# design.net
KiCad netlist of a schematic drawn in EasyEDA Pro
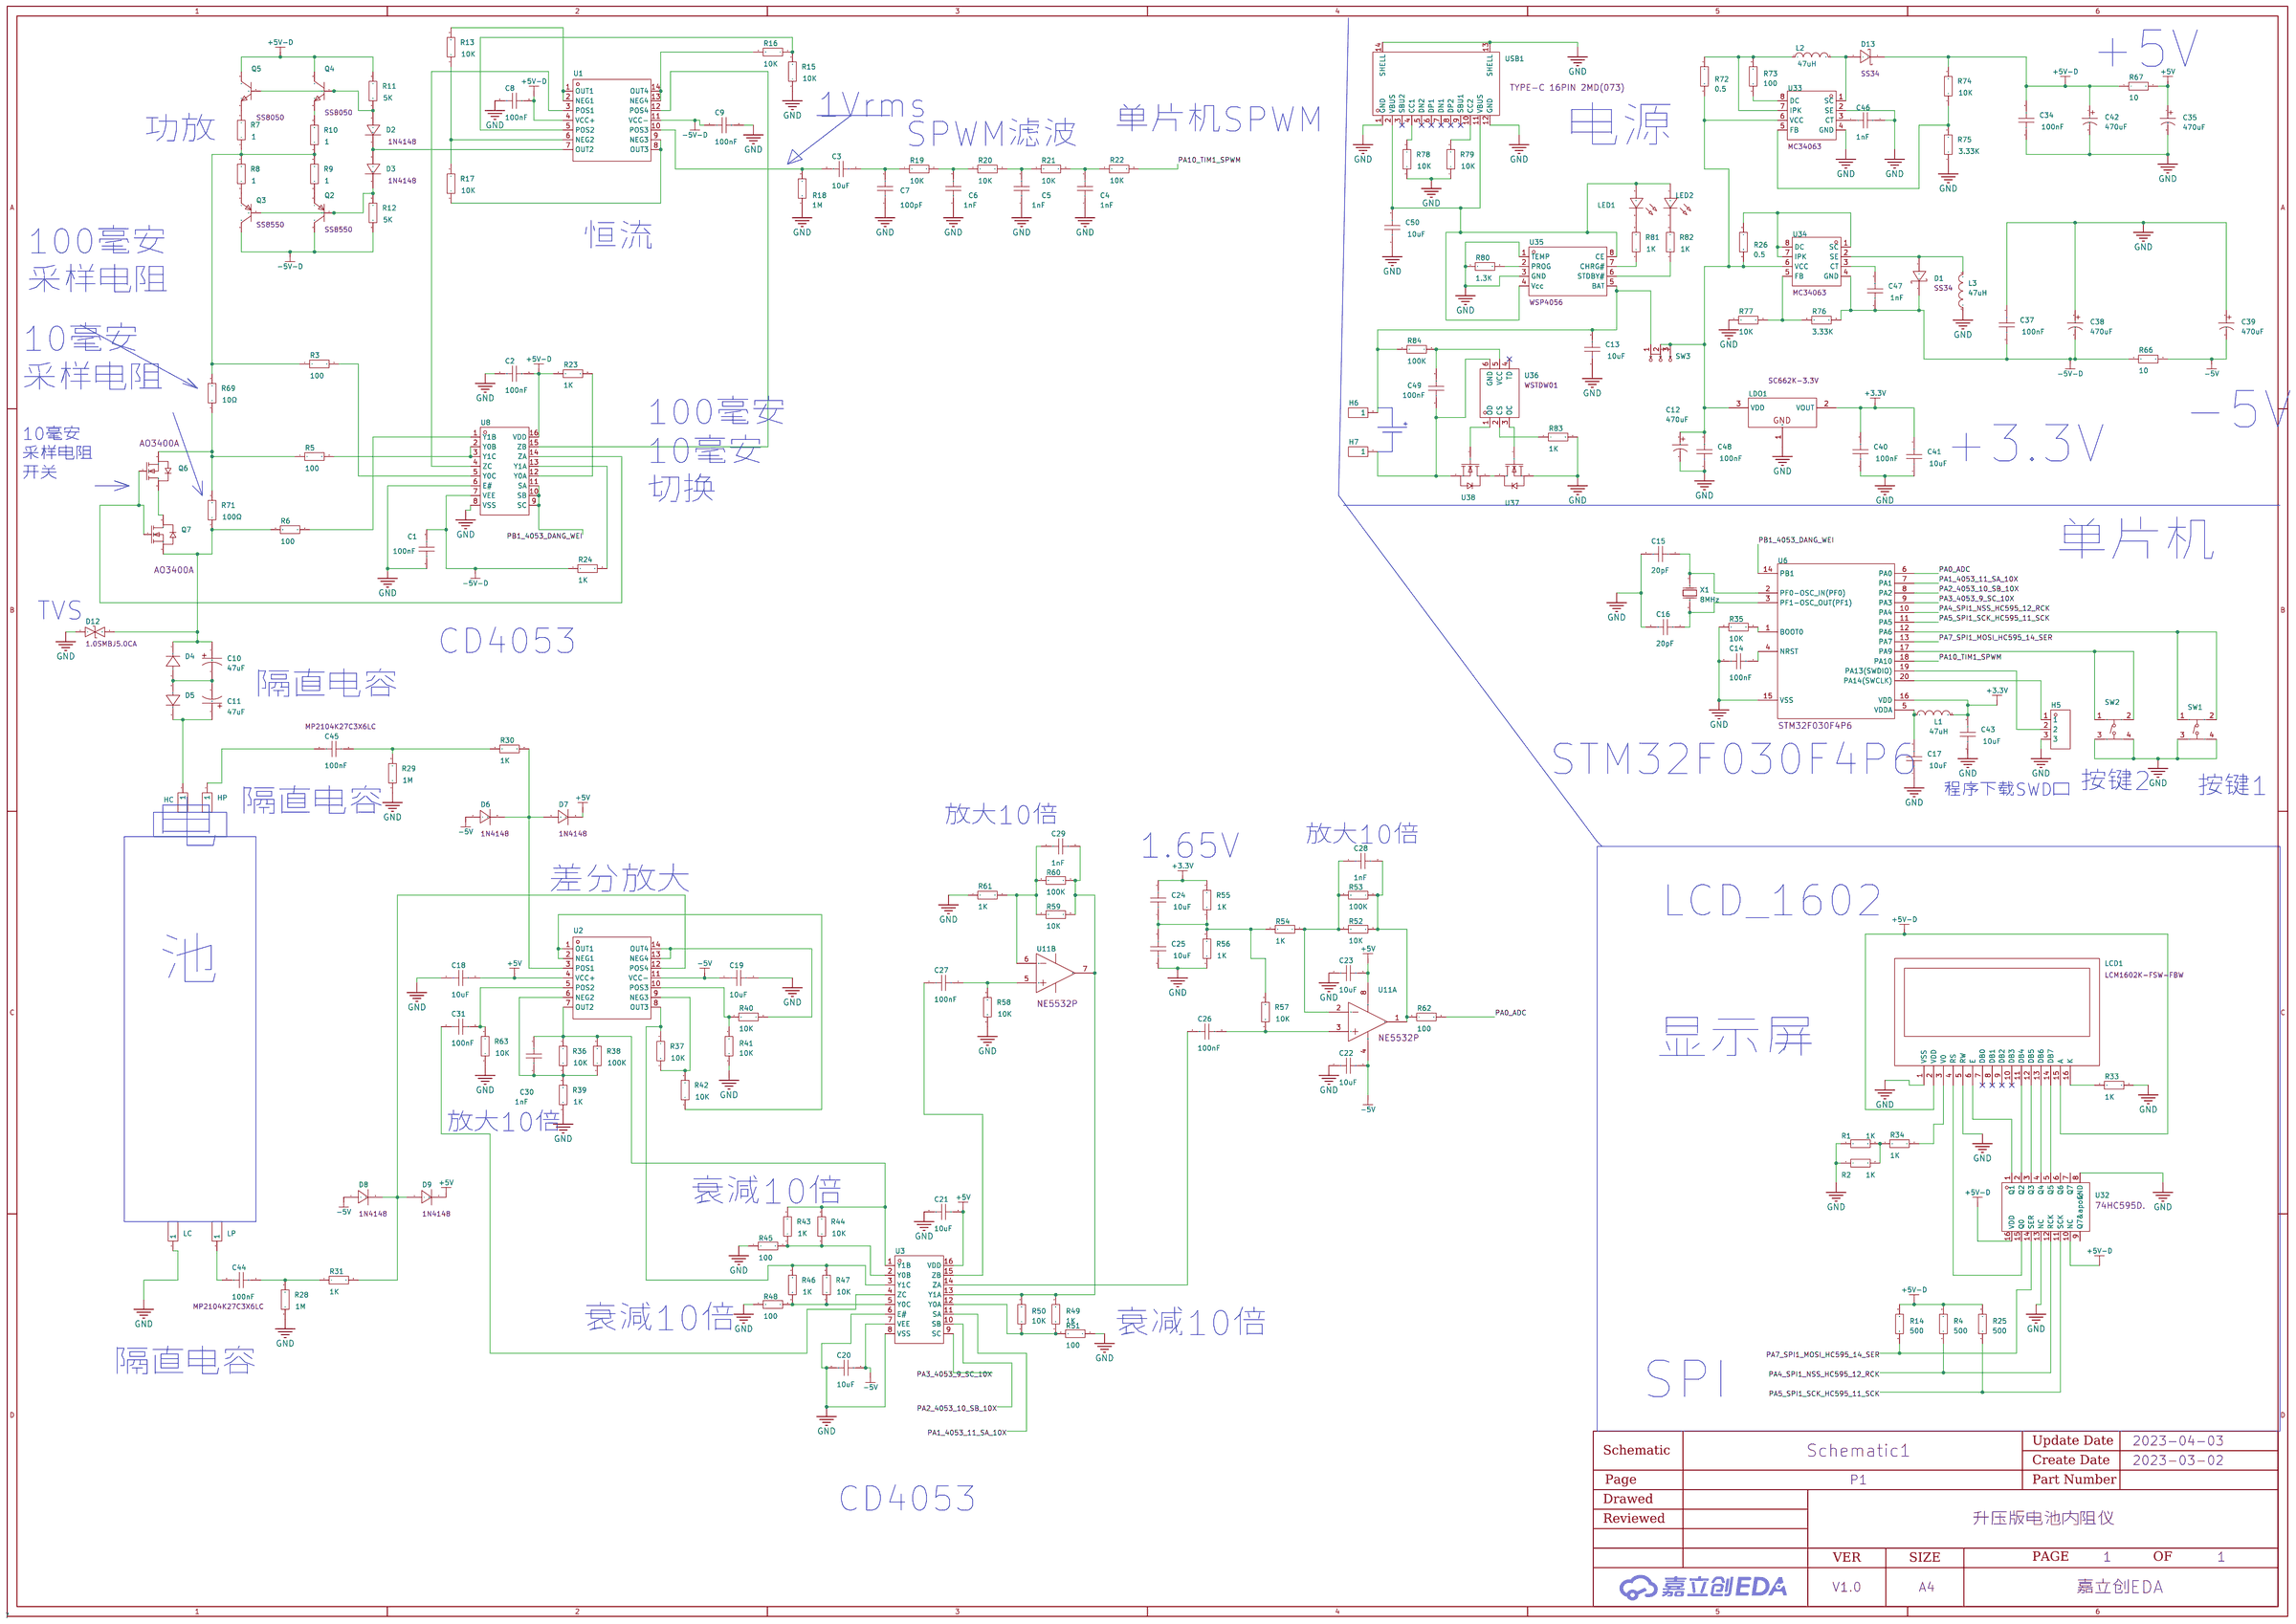
[diagram p0: schematic sheet]

(export (version "E")
  (design (tool "Eeschema 10.0.6"))
  (components
    (comp (ref "C1")
      (value "100nF")
      (footprint "easyedapro:C0603")
      (libsource (lib "easyedapro") (part "CapAcitance"))
    )
    (comp (ref "C2")
      (value "100nF")
      (footprint "easyedapro:C0603")
      (libsource (lib "easyedapro") (part "CapAcitance"))
    )
    (comp (ref "C3")
      (value "10uF")
      (footprint "easyedapro:C0603")
      (libsource (lib "easyedapro") (part "CapAcitance"))
    )
    (comp (ref "C4")
      (value "1nF")
      (footprint "easyedapro:C0603")
      (libsource (lib "easyedapro") (part "CapAcitance"))
    )
    (comp (ref "C5")
      (value "1nF")
      (footprint "easyedapro:C0603")
      (libsource (lib "easyedapro") (part "CapAcitance"))
    )
    (comp (ref "C6")
      (value "1nF")
      (footprint "easyedapro:C0603")
      (libsource (lib "easyedapro") (part "CapAcitance"))
    )
    (comp (ref "C7")
      (value "100pF")
      (footprint "easyedapro:C0603")
      (libsource (lib "easyedapro") (part "CapAcitance"))
    )
    (comp (ref "C8")
      (value "100nF")
      (footprint "easyedapro:C0603")
      (libsource (lib "easyedapro") (part "CapAcitance"))
    )
    (comp (ref "C9")
      (value "100nF")
      (footprint "easyedapro:C0603")
      (libsource (lib "easyedapro") (part "CapAcitance"))
    )
    (comp (ref "C10")
      (value "47uF")
      (footprint "easyedapro:CAP-TH_BD10.0-P5.00-D1.0-FD")
      (description "容值:47uF;精度:±20%;额定电压:200V;电容体直径:10mm;电容体长度:20mm;脚间距:5mm;工作寿命:5000hrs@105℃;")
      (fields (field (name "Manufacturer Part") "KF470M200G200A") (field (name "Manufacturer") "CapXon(丰宾)"))
      (libsource (lib "easyedapro") (part "KF470M200G200A"))
    )
    (comp (ref "C11")
      (value "47uF")
      (footprint "easyedapro:CAP-TH_BD10.0-P5.00-D1.0-FD")
      (description "容值:47uF;精度:±20%;额定电压:200V;电容体直径:10mm;电容体长度:20mm;脚间距:5mm;工作寿命:5000hrs@105℃;")
      (fields (field (name "Manufacturer Part") "KF470M200G200A") (field (name "Manufacturer") "CapXon(丰宾)"))
      (libsource (lib "easyedapro") (part "KF470M200G200A"))
    )
    (comp (ref "C12")
      (value "470uF")
      (footprint "easyedapro:CAP-TH_BD8.0-P3.50-D0.6-FD")
      (description "容值:470uF;精度:±20%;额定电压:16V;电容体直径:8mm;电容体长度:12mm;脚间距:3.5mm;工作寿命:2000hrs@105℃;")
      (fields
        (field (name "Manufacturer Part") "KM477M016F12RR0VH2FP0")
        (field (name "Manufacturer") "CX(承兴)")
      )
      (libsource (lib "easyedapro") (part "470uf16v"))
    )
    (comp (ref "C13")
      (value "10uF")
      (footprint "easyedapro:C0603")
      (libsource (lib "easyedapro") (part "CapAcitance"))
    )
    (comp (ref "C14")
      (value "100nF")
      (footprint "easyedapro:C0603")
      (libsource (lib "easyedapro") (part "CapAcitance"))
    )
    (comp (ref "C15")
      (value "20pF")
      (footprint "easyedapro:C0603")
      (libsource (lib "easyedapro") (part "CapAcitance"))
    )
    (comp (ref "C16")
      (value "20pF")
      (footprint "easyedapro:C0603")
      (libsource (lib "easyedapro") (part "CapAcitance"))
    )
    (comp (ref "C17")
      (value "10uF")
      (footprint "easyedapro:C0603")
      (libsource (lib "easyedapro") (part "CapAcitance"))
    )
    (comp (ref "C18")
      (value "10uF")
      (footprint "easyedapro:C0603")
      (libsource (lib "easyedapro") (part "CapAcitance"))
    )
    (comp (ref "C19")
      (value "10uF")
      (footprint "easyedapro:C0603")
      (libsource (lib "easyedapro") (part "CapAcitance"))
    )
    (comp (ref "C20")
      (value "10uF")
      (footprint "easyedapro:C0603")
      (libsource (lib "easyedapro") (part "CapAcitance"))
    )
    (comp (ref "C21")
      (value "10uF")
      (footprint "easyedapro:C0603")
      (libsource (lib "easyedapro") (part "CapAcitance"))
    )
    (comp (ref "C22")
      (value "10uF")
      (footprint "easyedapro:C0603")
      (libsource (lib "easyedapro") (part "CapAcitance"))
    )
    (comp (ref "C23")
      (value "10uF")
      (footprint "easyedapro:C0603")
      (libsource (lib "easyedapro") (part "CapAcitance"))
    )
    (comp (ref "C24")
      (value "10uF")
      (footprint "easyedapro:C0603")
      (libsource (lib "easyedapro") (part "CapAcitance"))
    )
    (comp (ref "C25")
      (value "10uF")
      (footprint "easyedapro:C0603")
      (libsource (lib "easyedapro") (part "CapAcitance"))
    )
    (comp (ref "C26")
      (value "100nF")
      (footprint "easyedapro:C0603")
      (libsource (lib "easyedapro") (part "CapAcitance"))
    )
    (comp (ref "C27")
      (value "100nF")
      (footprint "easyedapro:C0603")
      (libsource (lib "easyedapro") (part "CapAcitance"))
    )
    (comp (ref "C28")
      (value "1nF")
      (footprint "easyedapro:C0603")
      (libsource (lib "easyedapro") (part "CapAcitance"))
    )
    (comp (ref "C29")
      (value "1nF")
      (footprint "easyedapro:C0603")
      (libsource (lib "easyedapro") (part "CapAcitance"))
    )
    (comp (ref "C30")
      (value "1nF")
      (footprint "easyedapro:C0603")
      (libsource (lib "easyedapro") (part "CapAcitance"))
    )
    (comp (ref "C31")
      (value "100nF")
      (footprint "easyedapro:C0603")
      (libsource (lib "easyedapro") (part "CapAcitance"))
    )
    (comp (ref "C34")
      (value "100nF")
      (footprint "easyedapro:C0603")
      (libsource (lib "easyedapro") (part "CapAcitance"))
    )
    (comp (ref "C35")
      (value "470uF")
      (footprint "easyedapro:CAP-TH_BD8.0-P3.50-D0.6-FD")
      (description "容值:470uF;精度:±20%;额定电压:16V;电容体直径:8mm;电容体长度:12mm;脚间距:3.5mm;工作寿命:2000hrs@105℃;")
      (fields
        (field (name "Manufacturer Part") "KM477M016F12RR0VH2FP0")
        (field (name "Manufacturer") "CX(承兴)")
      )
      (libsource (lib "easyedapro") (part "470uf16v"))
    )
    (comp (ref "C37")
      (value "100nF")
      (footprint "easyedapro:C0603")
      (libsource (lib "easyedapro") (part "CapAcitance"))
    )
    (comp (ref "C38")
      (value "470uF")
      (footprint "easyedapro:CAP-TH_BD8.0-P3.50-D0.6-FD")
      (description "容值:470uF;精度:±20%;额定电压:16V;电容体直径:8mm;电容体长度:12mm;脚间距:3.5mm;工作寿命:2000hrs@105℃;")
      (fields
        (field (name "Manufacturer Part") "KM477M016F12RR0VH2FP0")
        (field (name "Manufacturer") "CX(承兴)")
      )
      (libsource (lib "easyedapro") (part "470uf16v"))
    )
    (comp (ref "C39")
      (value "470uF")
      (footprint "easyedapro:CAP-TH_BD8.0-P3.50-D0.6-FD")
      (description "容值:470uF;精度:±20%;额定电压:16V;电容体直径:8mm;电容体长度:12mm;脚间距:3.5mm;工作寿命:2000hrs@105℃;")
      (fields
        (field (name "Manufacturer Part") "KM477M016F12RR0VH2FP0")
        (field (name "Manufacturer") "CX(承兴)")
      )
      (libsource (lib "easyedapro") (part "470uf16v"))
    )
    (comp (ref "C40")
      (value "100nF")
      (footprint "easyedapro:C0603")
      (libsource (lib "easyedapro") (part "CapAcitance"))
    )
    (comp (ref "C41")
      (value "10uF")
      (footprint "easyedapro:C0603")
      (libsource (lib "easyedapro") (part "CapAcitance"))
    )
    (comp (ref "C42")
      (value "470uF")
      (footprint "easyedapro:CAP-TH_BD8.0-P3.50-D0.6-FD")
      (description "容值:470uF;精度:±20%;额定电压:16V;电容体直径:8mm;电容体长度:12mm;脚间距:3.5mm;工作寿命:2000hrs@105℃;")
      (fields
        (field (name "Manufacturer Part") "KM477M016F12RR0VH2FP0")
        (field (name "Manufacturer") "CX(承兴)")
      )
      (libsource (lib "easyedapro") (part "470uf16v"))
    )
    (comp (ref "C43")
      (value "10uF")
      (footprint "easyedapro:C0603")
      (libsource (lib "easyedapro") (part "CapAcitance"))
    )
    (comp (ref "C44")
      (value "100nF")
      (footprint "easyedapro:CAP-TH_L13.0-W6.0-P10.00-D1.0")
      (description "等级:X2;容值:100nF;精度:±10%;")
      (fields (field (name "Manufacturer Part") "MP2104K27C3X6LC") (field (name "Manufacturer") "SRD(圣融达)"))
      (libsource (lib "easyedapro") (part "MP2104KGC3XLC"))
    )
    (comp (ref "C45")
      (value "100nF")
      (footprint "easyedapro:CAP-TH_L13.0-W6.0-P10.00-D1.0")
      (description "等级:X2;容值:100nF;精度:±10%;")
      (fields (field (name "Manufacturer Part") "MP2104K27C3X6LC") (field (name "Manufacturer") "SRD(圣融达)"))
      (libsource (lib "easyedapro") (part "MP2104KGC3XLC"))
    )
    (comp (ref "C46")
      (value "1nF")
      (footprint "easyedapro:C0603")
      (libsource (lib "easyedapro") (part "CapAcitance"))
    )
    (comp (ref "C47")
      (value "1nF")
      (footprint "easyedapro:C0603")
      (libsource (lib "easyedapro") (part "CapAcitance"))
    )
    (comp (ref "C48")
      (value "100nF")
      (footprint "easyedapro:C0603")
      (libsource (lib "easyedapro") (part "CapAcitance"))
    )
    (comp (ref "C49")
      (value "100nF")
      (footprint "easyedapro:C0603")
      (libsource (lib "easyedapro") (part "CapAcitance"))
    )
    (comp (ref "C50")
      (value "10uF")
      (footprint "easyedapro:C0603")
      (libsource (lib "easyedapro") (part "CapAcitance"))
    )
    (comp (ref "D1")
      (value "SS34")
      (footprint "easyedapro:SMA_L4.3-W2.6-LS5.2-RD")
      (description "二极管配置:独立式;直流反向耐压(Vr):40V;平均整流电流(Io):3A;正向压降(Vf):550mV@3A;反向电流(Ir):500uA@40V;")
      (fields (field (name "Manufacturer Part") "SS34") (field (name "Manufacturer") "MDD"))
      (libsource (lib "easyedapro") (part "SS34_C8678"))
    )
    (comp (ref "D2")
      (value "1N4148")
      (footprint "easyedapro:DO-35_BD2.0-L4.0-P8.00-D0.5-FD")
      (fields (field (name "Manufacturer Part") "1N4148") (field (name "Manufacturer") "ST(先科)"))
      (libsource (lib "easyedapro") (part "1N4148"))
    )
    (comp (ref "D3")
      (value "1N4148")
      (footprint "easyedapro:DO-35_BD2.0-L4.0-P8.00-D0.5-FD")
      (fields (field (name "Manufacturer Part") "1N4148") (field (name "Manufacturer") "ST(先科)"))
      (libsource (lib "easyedapro") (part "1N4148"))
    )
    (comp (ref "D4")
      (value "~")
      (footprint "easyedapro:DO_1N4007")
      (libsource (lib "easyedapro") (part "D_1N4007"))
    )
    (comp (ref "D5")
      (value "~")
      (footprint "easyedapro:DO_1N4007")
      (libsource (lib "easyedapro") (part "D_1N4007"))
    )
    (comp (ref "D6")
      (value "1N4148")
      (footprint "easyedapro:DO-35_BD2.0-L4.0-P8.00-D0.5-FD")
      (fields (field (name "Manufacturer Part") "1N4148") (field (name "Manufacturer") "ST(先科)"))
      (libsource (lib "easyedapro") (part "1N4148"))
    )
    (comp (ref "D7")
      (value "1N4148")
      (footprint "easyedapro:DO-35_BD2.0-L4.0-P8.00-D0.5-FD")
      (fields (field (name "Manufacturer Part") "1N4148") (field (name "Manufacturer") "ST(先科)"))
      (libsource (lib "easyedapro") (part "1N4148"))
    )
    (comp (ref "D8")
      (value "1N4148")
      (footprint "easyedapro:DO-35_BD2.0-L4.0-P8.00-D0.5-FD")
      (fields (field (name "Manufacturer Part") "1N4148") (field (name "Manufacturer") "ST(先科)"))
      (libsource (lib "easyedapro") (part "1N4148"))
    )
    (comp (ref "D9")
      (value "1N4148")
      (footprint "easyedapro:DO-35_BD2.0-L4.0-P8.00-D0.5-FD")
      (fields (field (name "Manufacturer Part") "1N4148") (field (name "Manufacturer") "ST(先科)"))
      (libsource (lib "easyedapro") (part "1N4148"))
    )
    (comp (ref "D12")
      (value "1.0SMBJ5.0CA")
      (footprint "easyedapro:SMB_L4.6-W3.6-LS5.3-BI")
      (description "极性:双向;反向截止电压(Vrwm):5V;击穿电压:6.4V;峰值脉冲电流(Ipp)@10/1000s:108.7A;最大钳位电压:9.2V;")
      (fields (field (name "Manufacturer Part") "1.0SMBJ5.0CA") (field (name "Manufacturer") "BORN(伯恩半导体)"))
      (libsource (lib "easyedapro") (part "1.0SMBJ5.0CA"))
    )
    (comp (ref "D13")
      (value "SS34")
      (footprint "easyedapro:SMA_L4.3-W2.6-LS5.2-RD")
      (description "二极管配置:独立式;直流反向耐压(Vr):40V;平均整流电流(Io):3A;正向压降(Vf):550mV@3A;反向电流(Ir):500uA@40V;")
      (fields (field (name "Manufacturer Part") "SS34") (field (name "Manufacturer") "MDD"))
      (libsource (lib "easyedapro") (part "SS34_C8678"))
    )
    (comp (ref "H5")
      (value "~")
      (footprint "easyedapro:HDR-TH_3P-P2.54-V-M")
      (libsource (lib "easyedapro") (part "PZ254V-11-03P_C2937625"))
    )
    (comp (ref "H6")
      (value "~")
      (footprint "easyedapro:HDR-TH_1P-V-M_XKB_X4611WV-01I-C28D40")
      (libsource (lib "easyedapro") (part "HDR_1x1"))
    )
    (comp (ref "H7")
      (value "~")
      (footprint "easyedapro:HDR-TH_1P-V-M_XKB_X4611WV-01I-C28D40")
      (libsource (lib "easyedapro") (part "HDR_1x1"))
    )
    (comp (ref "HC")
      (value "~")
      (footprint "easyedapro:HDR-TH_1P-V-M_XKB_X4611WV-01I-C28D40")
      (libsource (lib "easyedapro") (part "HDR_1x1"))
    )
    (comp (ref "HP")
      (value "~")
      (footprint "easyedapro:HDR-TH_1P-V-M_XKB_X4611WV-01I-C28D40")
      (libsource (lib "easyedapro") (part "HDR_1x1"))
    )
    (comp (ref "L1")
      (value "47uH")
      (footprint "easyedapro:IND-SMD_L4.5-W4.0_SLF0403")
      (description "电感值:47uH;直流电阻(DCR):844mΩ;精度:±10%;额定电流:540mA;")
      (fields
        (field (name "Manufacturer Part") "SLF0403-470KTT")
        (field (name "Manufacturer") "Sunltech(韩国顺磁)")
      )
      (libsource (lib "easyedapro") (part "SLF0403-470KTT"))
    )
    (comp (ref "L2")
      (value "47uH")
      (footprint "easyedapro:IND-SMD_L4.5-W4.0_SLF0403")
      (description "电感值:47uH;直流电阻(DCR):844mΩ;精度:±10%;额定电流:540mA;")
      (fields
        (field (name "Manufacturer Part") "SLF0403-470KTT")
        (field (name "Manufacturer") "Sunltech(韩国顺磁)")
      )
      (libsource (lib "easyedapro") (part "SLF0403-470KTT"))
    )
    (comp (ref "L3")
      (value "47uH")
      (footprint "easyedapro:IND-SMD_L4.5-W4.0_SLF0403")
      (description "电感值:47uH;直流电阻(DCR):844mΩ;精度:±10%;额定电流:540mA;")
      (fields
        (field (name "Manufacturer Part") "SLF0403-470KTT")
        (field (name "Manufacturer") "Sunltech(韩国顺磁)")
      )
      (libsource (lib "easyedapro") (part "SLF0403-470KTT"))
    )
    (comp (ref "LC")
      (value "~")
      (footprint "easyedapro:HDR-TH_1P-V-M_XKB_X4611WV-01I-C28D40")
      (libsource (lib "easyedapro") (part "HDR_1x1"))
    )
    (comp (ref "LCD1")
      (value "LCM1602K-FSW-FBW")
      (footprint "easyedapro:MODULE-TH_LCM1602K")
      (description "尺寸(inch):-;主控芯片:KS0066U;")
      (fields
        (field (name "Manufacturer Part") "LCM1602K-FSW-FBW")
        (field (name "Manufacturer") "LONTECH(厦门龙特)")
      )
      (libsource (lib "easyedapro") (part "LCM1602K-FSW-FBW"))
    )
    (comp (ref "LDO1")
      (value "SC662K-3.3V")
      (footprint "easyedapro:SOT-23-3_L2.9-W1.3-P1.90-LS2.4-BR")
      (description "输出类型:固定;输出极性:正;最大输入电压:6V;输出电压:3.3V;输出电流:250mA;电源纹波抑制比(PSRR):50dB@(1kHz);")
      (fields (field (name "Manufacturer Part") "SC662K-3.3V") (field (name "Manufacturer") "FM(富满)"))
      (libsource (lib "easyedapro") (part "SC662K-3.3V"))
    )
    (comp (ref "LED1")
      (value "~")
      (footprint "easyedapro:LED_TH-3mm")
      (libsource (lib "easyedapro") (part "LED_TH-R"))
    )
    (comp (ref "LED2")
      (value "~")
      (footprint "easyedapro:LED_TH-3mm")
      (libsource (lib "easyedapro") (part "LED_TH-R"))
    )
    (comp (ref "LP")
      (value "~")
      (footprint "easyedapro:HDR-TH_1P-V-M_XKB_X4611WV-01I-C28D40")
      (libsource (lib "easyedapro") (part "HDR_1x1"))
    )
    (comp (ref "Q2")
      (value "SS8550")
      (footprint "easyedapro:SOT-23-3_L2.9-W1.6-P1.90-LS2.8-BR")
      (fields (field (name "Manufacturer Part") "SS8550") (field (name "Manufacturer") "ElecSuper(静芯微）"))
      (libsource (lib "easyedapro") (part "SS8550_C5249677"))
    )
    (comp (ref "Q3")
      (value "SS8550")
      (footprint "easyedapro:SOT-23-3_L2.9-W1.6-P1.90-LS2.8-BR")
      (fields (field (name "Manufacturer Part") "SS8550") (field (name "Manufacturer") "ElecSuper(静芯微）"))
      (libsource (lib "easyedapro") (part "SS8550_C5249677"))
    )
    (comp (ref "Q4")
      (value "SS8050")
      (footprint "easyedapro:SOT-23-3_L2.9-W1.6-P1.90-LS2.8-BR")
      (fields (field (name "Manufacturer Part") "SS8050") (field (name "Manufacturer") "ElecSuper(静芯微）"))
      (libsource (lib "easyedapro") (part "SS8050_C5249676"))
    )
    (comp (ref "Q5")
      (value "SS8050")
      (footprint "easyedapro:SOT-23-3_L2.9-W1.6-P1.90-LS2.8-BR")
      (fields (field (name "Manufacturer Part") "SS8050") (field (name "Manufacturer") "ElecSuper(静芯微）"))
      (libsource (lib "easyedapro") (part "SS8050_C5249676"))
    )
    (comp (ref "Q6")
      (value "AO3400A")
      (footprint "easyedapro:SOT-23-3_L2.9-W1.3-P1.90-LS2.4-BR")
      (fields (field (name "Manufacturer Part") "AO3400A") (field (name "Manufacturer") "UMW(广东友台半导体)"))
      (libsource (lib "easyedapro") (part "AO3400A_C347475"))
    )
    (comp (ref "Q7")
      (value "AO3400A")
      (footprint "easyedapro:SOT-23-3_L2.9-W1.3-P1.90-LS2.4-BR")
      (fields (field (name "Manufacturer Part") "AO3400A") (field (name "Manufacturer") "UMW(广东友台半导体)"))
      (libsource (lib "easyedapro") (part "AO3400A_C347475"))
    )
    (comp (ref "R1")
      (value "1K")
      (footprint "easyedapro:Res_1/8W")
      (libsource (lib "easyedapro") (part "电阻"))
    )
    (comp (ref "R2")
      (value "1K")
      (footprint "easyedapro:Res_1/8W")
      (libsource (lib "easyedapro") (part "电阻"))
    )
    (comp (ref "R3")
      (value "100")
      (footprint "easyedapro:Res_1/8W")
      (libsource (lib "easyedapro") (part "电阻"))
    )
    (comp (ref "R4")
      (value "500")
      (footprint "easyedapro:Res_1/8W")
      (libsource (lib "easyedapro") (part "电阻"))
    )
    (comp (ref "R5")
      (value "100")
      (footprint "easyedapro:Res_1/8W")
      (libsource (lib "easyedapro") (part "电阻"))
    )
    (comp (ref "R6")
      (value "100")
      (footprint "easyedapro:Res_1/8W")
      (libsource (lib "easyedapro") (part "电阻"))
    )
    (comp (ref "R7") (value "1") (footprint "easyedapro:Res_1/8W") (libsource (lib "easyedapro") (part "电阻")))
    (comp (ref "R8") (value "1") (footprint "easyedapro:Res_1/8W") (libsource (lib "easyedapro") (part "电阻")))
    (comp (ref "R9") (value "1") (footprint "easyedapro:Res_1/8W") (libsource (lib "easyedapro") (part "电阻")))
    (comp (ref "R10")
      (value "1")
      (footprint "easyedapro:Res_1/8W")
      (libsource (lib "easyedapro") (part "电阻"))
    )
    (comp (ref "R11")
      (value "5K")
      (footprint "easyedapro:Res_1/8W")
      (libsource (lib "easyedapro") (part "电阻"))
    )
    (comp (ref "R12")
      (value "5K")
      (footprint "easyedapro:Res_1/8W")
      (libsource (lib "easyedapro") (part "电阻"))
    )
    (comp (ref "R13")
      (value "10K")
      (footprint "easyedapro:Res_1/8W")
      (libsource (lib "easyedapro") (part "电阻"))
    )
    (comp (ref "R14")
      (value "500")
      (footprint "easyedapro:Res_1/8W")
      (libsource (lib "easyedapro") (part "电阻"))
    )
    (comp (ref "R15")
      (value "10K")
      (footprint "easyedapro:Res_1/8W")
      (libsource (lib "easyedapro") (part "电阻"))
    )
    (comp (ref "R16")
      (value "10K")
      (footprint "easyedapro:Res_1/8W")
      (libsource (lib "easyedapro") (part "电阻"))
    )
    (comp (ref "R17")
      (value "10K")
      (footprint "easyedapro:Res_1/8W")
      (libsource (lib "easyedapro") (part "电阻"))
    )
    (comp (ref "R18")
      (value "1M")
      (footprint "easyedapro:Res_1/8W")
      (libsource (lib "easyedapro") (part "电阻"))
    )
    (comp (ref "R19")
      (value "10K")
      (footprint "easyedapro:Res_1/8W")
      (libsource (lib "easyedapro") (part "电阻"))
    )
    (comp (ref "R20")
      (value "10K")
      (footprint "easyedapro:Res_1/8W")
      (libsource (lib "easyedapro") (part "电阻"))
    )
    (comp (ref "R21")
      (value "10K")
      (footprint "easyedapro:Res_1/8W")
      (libsource (lib "easyedapro") (part "电阻"))
    )
    (comp (ref "R22")
      (value "10K")
      (footprint "easyedapro:Res_1/8W")
      (libsource (lib "easyedapro") (part "电阻"))
    )
    (comp (ref "R23")
      (value "1K")
      (footprint "easyedapro:Res_1/8W")
      (libsource (lib "easyedapro") (part "电阻"))
    )
    (comp (ref "R24")
      (value "1K")
      (footprint "easyedapro:Res_1/8W")
      (libsource (lib "easyedapro") (part "电阻"))
    )
    (comp (ref "R25")
      (value "500")
      (footprint "easyedapro:Res_1/8W")
      (libsource (lib "easyedapro") (part "电阻"))
    )
    (comp (ref "R26") (value "0.5") (footprint "easyedapro:R0603") (libsource (lib "easyedapro") (part "电阻")))
    (comp (ref "R28")
      (value "1M")
      (footprint "easyedapro:Res_1/8W")
      (libsource (lib "easyedapro") (part "电阻"))
    )
    (comp (ref "R29")
      (value "1M")
      (footprint "easyedapro:Res_1/8W")
      (libsource (lib "easyedapro") (part "电阻"))
    )
    (comp (ref "R30")
      (value "1K")
      (footprint "easyedapro:Res_1/8W")
      (libsource (lib "easyedapro") (part "电阻"))
    )
    (comp (ref "R31")
      (value "1K")
      (footprint "easyedapro:Res_1/8W")
      (libsource (lib "easyedapro") (part "电阻"))
    )
    (comp (ref "R33")
      (value "1K")
      (footprint "easyedapro:Res_1/8W")
      (libsource (lib "easyedapro") (part "电阻"))
    )
    (comp (ref "R34")
      (value "1K")
      (footprint "easyedapro:Res_1/8W")
      (libsource (lib "easyedapro") (part "电阻"))
    )
    (comp (ref "R35")
      (value "10K")
      (footprint "easyedapro:Res_1/8W")
      (libsource (lib "easyedapro") (part "电阻"))
    )
    (comp (ref "R36")
      (value "10K")
      (footprint "easyedapro:Res_1/8W")
      (libsource (lib "easyedapro") (part "电阻"))
    )
    (comp (ref "R37")
      (value "10K")
      (footprint "easyedapro:Res_1/8W")
      (libsource (lib "easyedapro") (part "电阻"))
    )
    (comp (ref "R38")
      (value "100K")
      (footprint "easyedapro:Res_1/8W")
      (libsource (lib "easyedapro") (part "电阻"))
    )
    (comp (ref "R39")
      (value "1K")
      (footprint "easyedapro:Res_1/8W")
      (libsource (lib "easyedapro") (part "电阻"))
    )
    (comp (ref "R40")
      (value "10K")
      (footprint "easyedapro:Res_1/8W")
      (libsource (lib "easyedapro") (part "电阻"))
    )
    (comp (ref "R41")
      (value "10K")
      (footprint "easyedapro:Res_1/8W")
      (libsource (lib "easyedapro") (part "电阻"))
    )
    (comp (ref "R42")
      (value "10K")
      (footprint "easyedapro:Res_1/8W")
      (libsource (lib "easyedapro") (part "电阻"))
    )
    (comp (ref "R43")
      (value "1K")
      (footprint "easyedapro:Res_1/8W")
      (libsource (lib "easyedapro") (part "电阻"))
    )
    (comp (ref "R44")
      (value "10K")
      (footprint "easyedapro:Res_1/8W")
      (libsource (lib "easyedapro") (part "电阻"))
    )
    (comp (ref "R45")
      (value "100")
      (footprint "easyedapro:Res_1/8W")
      (libsource (lib "easyedapro") (part "电阻"))
    )
    (comp (ref "R46")
      (value "1K")
      (footprint "easyedapro:Res_1/8W")
      (libsource (lib "easyedapro") (part "电阻"))
    )
    (comp (ref "R47")
      (value "10K")
      (footprint "easyedapro:Res_1/8W")
      (libsource (lib "easyedapro") (part "电阻"))
    )
    (comp (ref "R48")
      (value "100")
      (footprint "easyedapro:Res_1/8W")
      (libsource (lib "easyedapro") (part "电阻"))
    )
    (comp (ref "R49")
      (value "1K")
      (footprint "easyedapro:Res_1/8W")
      (libsource (lib "easyedapro") (part "电阻"))
    )
    (comp (ref "R50")
      (value "10K")
      (footprint "easyedapro:Res_1/8W")
      (libsource (lib "easyedapro") (part "电阻"))
    )
    (comp (ref "R51")
      (value "100")
      (footprint "easyedapro:Res_1/8W")
      (libsource (lib "easyedapro") (part "电阻"))
    )
    (comp (ref "R52")
      (value "10K")
      (footprint "easyedapro:Res_1/8W")
      (libsource (lib "easyedapro") (part "电阻"))
    )
    (comp (ref "R53")
      (value "100K")
      (footprint "easyedapro:Res_1/8W")
      (libsource (lib "easyedapro") (part "电阻"))
    )
    (comp (ref "R54")
      (value "1K")
      (footprint "easyedapro:Res_1/8W")
      (libsource (lib "easyedapro") (part "电阻"))
    )
    (comp (ref "R55")
      (value "1K")
      (footprint "easyedapro:Res_1/8W")
      (libsource (lib "easyedapro") (part "电阻"))
    )
    (comp (ref "R56")
      (value "1K")
      (footprint "easyedapro:Res_1/8W")
      (libsource (lib "easyedapro") (part "电阻"))
    )
    (comp (ref "R57")
      (value "10K")
      (footprint "easyedapro:Res_1/8W")
      (libsource (lib "easyedapro") (part "电阻"))
    )
    (comp (ref "R58")
      (value "10K")
      (footprint "easyedapro:Res_1/8W")
      (libsource (lib "easyedapro") (part "电阻"))
    )
    (comp (ref "R59")
      (value "10K")
      (footprint "easyedapro:Res_1/8W")
      (libsource (lib "easyedapro") (part "电阻"))
    )
    (comp (ref "R60")
      (value "100K")
      (footprint "easyedapro:Res_1/8W")
      (libsource (lib "easyedapro") (part "电阻"))
    )
    (comp (ref "R61")
      (value "1K")
      (footprint "easyedapro:Res_1/8W")
      (libsource (lib "easyedapro") (part "电阻"))
    )
    (comp (ref "R62")
      (value "100")
      (footprint "easyedapro:Res_1/8W")
      (libsource (lib "easyedapro") (part "电阻"))
    )
    (comp (ref "R63")
      (value "10K")
      (footprint "easyedapro:Res_1/8W")
      (libsource (lib "easyedapro") (part "电阻"))
    )
    (comp (ref "R66") (value "10") (footprint "easyedapro:R0603") (libsource (lib "easyedapro") (part "电阻")))
    (comp (ref "R67") (value "10") (footprint "easyedapro:R0603") (libsource (lib "easyedapro") (part "电阻")))
    (comp (ref "R69")
      (value "10Ω")
      (footprint "easyedapro:R2512")
      (description "电阻类型:厚膜电阻;阻值:10Ω;精度:±5%;功率:2W;温度系数:±200ppm/℃;最大工作电压:200V;工作温度范围:-55℃~+155℃;")
      (fields (field (name "Manufacturer Part") "RC2512JK-7W10RL") (field (name "Manufacturer") "YAGEO(国巨)"))
      (libsource (lib "easyedapro") (part "RC2512JK-7W10RL"))
    )
    (comp (ref "R71")
      (value "100Ω")
      (footprint "easyedapro:R0603")
      (description "电阻类型:厚膜电阻;阻值:100Ω;精度:±1%;功率:100mW;温度系数:±100ppm/℃;最大工作电压:75V;工作温度范围:-55℃~+155℃;")
      (fields (field (name "Manufacturer Part") "AC0603FR-07100RL") (field (name "Manufacturer") "YAGEO(国巨)"))
      (libsource (lib "easyedapro") (part "AC0603FR-07100RL"))
    )
    (comp (ref "R72") (value "0.5") (footprint "easyedapro:R0603") (libsource (lib "easyedapro") (part "电阻")))
    (comp (ref "R73") (value "100") (footprint "easyedapro:R0603") (libsource (lib "easyedapro") (part "电阻")))
    (comp (ref "R74") (value "10K") (footprint "easyedapro:R0603") (libsource (lib "easyedapro") (part "电阻")))
    (comp (ref "R75")
      (value "3.33K")
      (footprint "easyedapro:R0603")
      (libsource (lib "easyedapro") (part "电阻"))
    )
    (comp (ref "R76")
      (value "3.33K")
      (footprint "easyedapro:R0603")
      (libsource (lib "easyedapro") (part "电阻"))
    )
    (comp (ref "R77") (value "10K") (footprint "easyedapro:R0603") (libsource (lib "easyedapro") (part "电阻")))
    (comp (ref "R78") (value "10K") (footprint "easyedapro:R0603") (libsource (lib "easyedapro") (part "电阻")))
    (comp (ref "R79") (value "10K") (footprint "easyedapro:R0603") (libsource (lib "easyedapro") (part "电阻")))
    (comp (ref "R80")
      (value "1.3K")
      (footprint "easyedapro:R0603")
      (libsource (lib "easyedapro") (part "电阻"))
    )
    (comp (ref "R81") (value "1K") (footprint "easyedapro:R0603") (libsource (lib "easyedapro") (part "电阻")))
    (comp (ref "R82") (value "1K") (footprint "easyedapro:R0603") (libsource (lib "easyedapro") (part "电阻")))
    (comp (ref "R83") (value "1K") (footprint "easyedapro:R0603") (libsource (lib "easyedapro") (part "电阻")))
    (comp (ref "R84")
      (value "100K")
      (footprint "easyedapro:R0603")
      (libsource (lib "easyedapro") (part "电阻"))
    )
    (comp (ref "SW1")
      (value "1TS005A-2600-5001")
      (footprint "easyedapro:SW-TH_4P-L6.0-W6.0-P4.50-LS6.5")
      (fields (field (name "Manufacturer") "HYP(鸿源精密)"))
      (libsource (lib "easyedapro") (part "1TS005A-2600-5001"))
    )
    (comp (ref "SW2")
      (value "1TS005A-2600-5001")
      (footprint "easyedapro:SW-TH_4P-L6.0-W6.0-P4.50-LS6.5")
      (fields (field (name "Manufacturer") "HYP(鸿源精密)"))
      (libsource (lib "easyedapro") (part "1TS005A-2600-5001"))
    )
    (comp (ref "SW3")
      (value "SS-12F20-G070")
      (footprint "easyedapro:SW-TH_G-SWITCH_SS-12F20-G070")
      (fields (field (name "Manufacturer") "G-Switch(品赞)"))
      (libsource (lib "easyedapro") (part "SS-12F20-G070"))
    )
    (comp (ref "U1")
      (value "TL084CN")
      (footprint "easyedapro:DIP-14_L17.8-W10.2-P2.54-BL")
      (description "运放类型:J-FET;放大器组数:4;增益带宽积（GBP）:4MHz;压摆率（SR）:16 V/us;电源电压:6V ~ 36V, ±3V ~ 18V;各通道供电电流:1.4mA;")
      (fields (field (name "Manufacturer") "TI(德州仪器)"))
      (libsource (lib "easyedapro") (part "TL084CN_C54501"))
    )
    (comp (ref "U2")
      (value "TL084CN")
      (footprint "easyedapro:DIP-14_L17.8-W10.2-P2.54-BL")
      (description "运放类型:J-FET;放大器组数:4;增益带宽积（GBP）:4MHz;压摆率（SR）:16 V/us;电源电压:6V ~ 36V, ±3V ~ 18V;各通道供电电流:1.4mA;")
      (fields (field (name "Manufacturer") "TI(德州仪器)"))
      (libsource (lib "easyedapro") (part "TL084CN_C54501"))
    )
    (comp (ref "U3")
      (value "CD4053BM/TR")
      (footprint "easyedapro:SOP-16_L9.9-W3.9-P1.27-LS6.1-BL")
      (fields (field (name "Manufacturer") "HGSEMI(华冠)"))
      (libsource (lib "easyedapro") (part "CD4053BM/TR"))
    )
    (comp (ref "U6")
      (value "STM32F030F4P6")
      (footprint "easyedapro:TSSOP-20_L6.5-W4.4-P0.65-LS6.4-BL")
      (fields (field (name "Manufacturer Part") "STM32F030F4P6") (field (name "Manufacturer") "ST(意法半导体)"))
      (libsource (lib "easyedapro") (part "STM32F030F4P6"))
    )
    (comp (ref "U8")
      (value "CD4053BM/TR")
      (footprint "easyedapro:SOP-16_L9.9-W3.9-P1.27-LS6.1-BL")
      (fields (field (name "Manufacturer") "HGSEMI(华冠)"))
      (libsource (lib "easyedapro") (part "CD4053BM/TR"))
    )
    (comp (ref "U11")
      (value "NE5532P")
      (footprint "easyedapro:DIP-8_L9.4-W6.4-P2.54-LS9.1-BL")
      (description "运放类型:General Purpose;放大器组数:2;增益带宽积（GBP）:10MHz;压摆率（SR）:9 V/us;电源电压:±5V ~ 15V;各通道供电电流:8mA;")
      (fields (field (name "Manufacturer Part") "NE5532P") (field (name "Manufacturer") "TI(德州仪器)"))
      (libsource (lib "easyedapro") (part "NE5532P"))
    )
    (comp (ref "U32")
      (value "74HC595D.")
      (footprint "easyedapro:SOP-16_L9.9-W3.9-P1.27-LS6.0-BL")
      (fields (field (name "Manufacturer Part") "74HC595D.") (field (name "Manufacturer") "FM(富满)"))
      (libsource (lib "easyedapro") (part "74HC595D."))
    )
    (comp (ref "U33")
      (value "MC34063")
      (footprint "easyedapro:SOIC-8_L5.0-W4.0-P1.27-LS6.0-BL")
      (fields (field (name "Manufacturer Part") "MC34063") (field (name "Manufacturer") "HXY MOSFET(华轩阳电子)"))
      (libsource (lib "easyedapro") (part "MC34063_C5349988"))
    )
    (comp (ref "U34")
      (value "MC34063")
      (footprint "easyedapro:SOIC-8_L5.0-W4.0-P1.27-LS6.0-BL")
      (fields (field (name "Manufacturer Part") "MC34063") (field (name "Manufacturer") "HXY MOSFET(华轩阳电子)"))
      (libsource (lib "easyedapro") (part "MC34063_C5349988"))
    )
    (comp (ref "U35")
      (value "WSP4056")
      (footprint "easyedapro:SOP-8_L5.1-W3.9-P1.27-LS6.0-BL")
      (fields (field (name "Manufacturer Part") "WSP4056") (field (name "Manufacturer") "WINSOK(微硕)"))
      (libsource (lib "easyedapro") (part "WSP4056"))
    )
    (comp (ref "U36")
      (value "WSTDW01")
      (footprint "easyedapro:SOT-23-6_L2.9-W1.6-P0.95-LS2.8-BR")
      (description "充电电池的类型:-;电池单元组数:-;最大充电电流:-;充满的电池组电压:-;最大供应电压:-;")
      (fields (field (name "Manufacturer Part") "WSTDW01") (field (name "Manufacturer") "WINSOK(微硕)"))
      (libsource (lib "easyedapro") (part "WSTDW01"))
    )
    (comp (ref "U37")
      (value "AO3400A")
      (footprint "easyedapro:SOT-23-3_L3.0-W1.6-P1.90-LS2.8-BR")
      (fields (field (name "Manufacturer") "ElecSuper(静芯微）"))
      (libsource (lib "easyedapro") (part "AO3400A_C5224194"))
    )
    (comp (ref "U38")
      (value "AO3400A")
      (footprint "easyedapro:SOT-23-3_L3.0-W1.6-P1.90-LS2.8-BR")
      (fields (field (name "Manufacturer") "ElecSuper(静芯微）"))
      (libsource (lib "easyedapro") (part "AO3400A_C5224194"))
    )
    (comp (ref "USB1")
      (value "TYPE-C 16PIN 2MD(073)")
      (footprint "easyedapro:USB-C-SMD_TYPE-C-6PIN-2MD-073")
      (description "连接器类型:Type-C;标准:-;公母:母座;触点数量:16;端口数量:1;安装方式:卧贴;额定电流 - 电源:5A;工作温度范围:-25℃~+85℃;")
      (fields
        (field (name "Manufacturer Part") "TYPE-C 16PIN 2MD(073)")
        (field (name "Manufacturer") "SHOU HAN(首韩)")
      )
      (libsource (lib "easyedapro") (part "TYPE-C 16PIN 2MD(073)"))
    )
    (comp (ref "X1")
      (value "8MHz")
      (footprint "easyedapro:OSC-TH_L10.0-W4.5-P5.00")
      (description "晶振类型:49S晶振;频率:8MHz;频率公差:±20ppm;频率稳定度:±30ppm;负载电容:20pF;工作温度:-20℃~+70℃;")
      (fields (field (name "Manufacturer Part") "X49SD8MSD2SC") (field (name "Manufacturer") "YXC(扬兴晶振)"))
      (libsource (lib "easyedapro") (part "X49SD8MSD2SC"))
    )
  )
  (nets
    (net (code "1") (name "+3.3V") (class "Default")
      (node (ref "C24") (pin "2") (pinfunction "2_2") (pintype "input"))
      (node (ref "C40") (pin "2") (pinfunction "2_2") (pintype "input"))
      (node (ref "C41") (pin "2") (pinfunction "2_2") (pintype "input"))
      (node (ref "C43") (pin "2") (pinfunction "2_2") (pintype "input"))
      (node (ref "L1") (pin "2") (pinfunction "2_2") (pintype "input"))
      (node (ref "LDO1") (pin "2") (pinfunction "VOUT_2") (pintype "input"))
      (node (ref "R55") (pin "2") (pinfunction "2_2") (pintype "input"))
      (node (ref "U6") (pin "16") (pinfunction "VDD_16") (pintype "input"))
    )
    (net (code "2") (name "+5V") (class "Default")
      (node (ref "C18") (pin "2") (pinfunction "2_2") (pintype "input"))
      (node (ref "C21") (pin "2") (pinfunction "2_2") (pintype "input"))
      (node (ref "C23") (pin "2") (pinfunction "2_2") (pintype "input"))
      (node (ref "C35") (pin "1") (pinfunction "1_1") (pintype "input"))
      (node (ref "D7") (pin "2") (pinfunction "C_2") (pintype "input"))
      (node (ref "D9") (pin "2") (pinfunction "C_2") (pintype "input"))
      (node (ref "R67") (pin "2") (pinfunction "2_2") (pintype "input"))
      (node (ref "U11") (pin "8") (pinfunction "VCC+_8") (pintype "input"))
      (node (ref "U2") (pin "4") (pinfunction "VCC+_4") (pintype "input"))
      (node (ref "U3") (pin "16") (pinfunction "VDD_16") (pintype "input"))
    )
    (net (code "3") (name "+5V-D") (class "Default")
      (node (ref "C2") (pin "2") (pinfunction "2_2") (pintype "input"))
      (node (ref "C34") (pin "2") (pinfunction "2_2") (pintype "input"))
      (node (ref "C42") (pin "1") (pinfunction "1_1") (pintype "input"))
      (node (ref "C8") (pin "2") (pinfunction "2_2") (pintype "input"))
      (node (ref "D13") (pin "1") (pinfunction "K_1") (pintype "input"))
      (node (ref "LCD1") (pin "15") (pinfunction "A_15") (pintype "input"))
      (node (ref "LCD1") (pin "2") (pinfunction "VDD_2") (pintype "input"))
      (node (ref "Q4") (pin "3") (pinfunction "C_3") (pintype "input"))
      (node (ref "Q5") (pin "3") (pinfunction "C_3") (pintype "input"))
      (node (ref "R11") (pin "2") (pinfunction "2_2") (pintype "input"))
      (node (ref "R14") (pin "2") (pinfunction "2_2") (pintype "input"))
      (node (ref "R23") (pin "1") (pinfunction "1_1") (pintype "input"))
      (node (ref "R25") (pin "2") (pinfunction "2_2") (pintype "input"))
      (node (ref "R4") (pin "2") (pinfunction "2_2") (pintype "input"))
      (node (ref "R67") (pin "1") (pinfunction "1_1") (pintype "input"))
      (node (ref "R74") (pin "2") (pinfunction "2_2") (pintype "input"))
      (node (ref "U1") (pin "4") (pinfunction "VCC+_4") (pintype "input"))
      (node (ref "U32") (pin "10") (pinfunction "NC_10") (pintype "input"))
      (node (ref "U32") (pin "16") (pinfunction "VDD_16") (pintype "input"))
      (node (ref "U8") (pin "16") (pinfunction "VDD_16") (pintype "input"))
    )
    (net (code "4") (name "-5V") (class "Default")
      (node (ref "C19") (pin "1") (pinfunction "1_1") (pintype "input"))
      (node (ref "C20") (pin "2") (pinfunction "2_2") (pintype "input"))
      (node (ref "C22") (pin "2") (pinfunction "2_2") (pintype "input"))
      (node (ref "C39") (pin "2") (pinfunction "2_2") (pintype "input"))
      (node (ref "D6") (pin "1") (pinfunction "A_1") (pintype "input"))
      (node (ref "D8") (pin "1") (pinfunction "A_1") (pintype "input"))
      (node (ref "R66") (pin "2") (pinfunction "2_2") (pintype "input"))
      (node (ref "U11") (pin "4") (pinfunction "VCC-_4") (pintype "input"))
      (node (ref "U2") (pin "11") (pinfunction "VCC-_11") (pintype "input"))
      (node (ref "U3") (pin "7") (pinfunction "VEE_7") (pintype "input"))
    )
    (net (code "5") (name "-5V-D") (class "Default")
      (node (ref "C1") (pin "2") (pinfunction "2_2") (pintype "input"))
      (node (ref "C37") (pin "1") (pinfunction "1_1") (pintype "input"))
      (node (ref "C38") (pin "2") (pinfunction "2_2") (pintype "input"))
      (node (ref "C47") (pin "1") (pinfunction "1_1") (pintype "input"))
      (node (ref "C9") (pin "1") (pinfunction "1_1") (pintype "input"))
      (node (ref "D1") (pin "1") (pinfunction "K_1") (pintype "input"))
      (node (ref "Q2") (pin "3") (pinfunction "C_3") (pintype "input"))
      (node (ref "Q3") (pin "3") (pinfunction "C_3") (pintype "input"))
      (node (ref "R12") (pin "1") (pinfunction "1_1") (pintype "input"))
      (node (ref "R24") (pin "1") (pinfunction "1_1") (pintype "input"))
      (node (ref "R66") (pin "1") (pinfunction "1_1") (pintype "input"))
      (node (ref "R76") (pin "2") (pinfunction "2_2") (pintype "input"))
      (node (ref "U1") (pin "11") (pinfunction "VCC-_11") (pintype "input"))
      (node (ref "U34") (pin "4") (pinfunction "GND_4") (pintype "input"))
      (node (ref "U8") (pin "7") (pinfunction "VEE_7") (pintype "input"))
    )
    (net (code "6") (name "/PA0_ADC") (class "Default")
      (node (ref "R62") (pin "2") (pinfunction "2_2") (pintype "input"))
      (node (ref "U6") (pin "6") (pinfunction "PA0_6") (pintype "bidirectional"))
    )
    (net (code "7") (name "/PA1_4053_11_SA_10X") (class "Default")
      (node (ref "U3") (pin "11") (pinfunction "SA_11") (pintype "input"))
      (node (ref "U6") (pin "7") (pinfunction "PA1_7") (pintype "bidirectional"))
    )
    (net (code "8") (name "/PA2_4053_10_SB_10X") (class "Default")
      (node (ref "U3") (pin "10") (pinfunction "SB_10") (pintype "input"))
      (node (ref "U6") (pin "8") (pinfunction "PA2_8") (pintype "bidirectional"))
    )
    (net (code "9") (name "/PA3_4053_9_SC_10X") (class "Default")
      (node (ref "U3") (pin "9") (pinfunction "SC_9") (pintype "input"))
      (node (ref "U6") (pin "9") (pinfunction "PA3_9") (pintype "bidirectional"))
    )
    (net (code "10") (name "/PA4_SPI1_NSS_HC595_12_RCK") (class "Default")
      (node (ref "R4") (pin "1") (pinfunction "1_1") (pintype "input"))
      (node (ref "U32") (pin "12") (pinfunction "RCK_12") (pintype "input"))
      (node (ref "U6") (pin "10") (pinfunction "PA4_10") (pintype "bidirectional"))
    )
    (net (code "11") (name "/PA5_SPI1_SCK_HC595_11_SCK") (class "Default")
      (node (ref "R25") (pin "1") (pinfunction "1_1") (pintype "input"))
      (node (ref "U32") (pin "11") (pinfunction "SCK_11") (pintype "input"))
      (node (ref "U6") (pin "11") (pinfunction "PA5_11") (pintype "bidirectional"))
    )
    (net (code "12") (name "/PA7_SPI1_MOSI_HC595_14_SER") (class "Default")
      (node (ref "R14") (pin "1") (pinfunction "1_1") (pintype "input"))
      (node (ref "U32") (pin "14") (pinfunction "SER_14") (pintype "input"))
      (node (ref "U6") (pin "13") (pinfunction "PA7_13") (pintype "bidirectional"))
    )
    (net (code "13") (name "/PA10_TIM1_SPWM") (class "Default")
      (node (ref "R22") (pin "2") (pinfunction "2_2") (pintype "input"))
      (node (ref "U6") (pin "18") (pinfunction "PA10_18") (pintype "bidirectional"))
    )
    (net (code "14") (name "/PB1_4053_DANG_WEI") (class "Default")
      (node (ref "U6") (pin "14") (pinfunction "PB1_14") (pintype "bidirectional"))
      (node (ref "U8") (pin "10") (pinfunction "SB_10") (pintype "input"))
      (node (ref "U8") (pin "11") (pinfunction "SA_11") (pintype "input"))
      (node (ref "U8") (pin "9") (pinfunction "SC_9") (pintype "input"))
    )
    (net (code "15") (name "GND") (class "Default")
      (node (ref "C1") (pin "1") (pinfunction "1_1") (pintype "input"))
      (node (ref "C12") (pin "2") (pinfunction "2_2") (pintype "input"))
      (node (ref "C13") (pin "1") (pinfunction "1_1") (pintype "input"))
      (node (ref "C14") (pin "2") (pinfunction "2_2") (pintype "input"))
      (node (ref "C15") (pin "2") (pinfunction "2_2") (pintype "input"))
      (node (ref "C16") (pin "2") (pinfunction "2_2") (pintype "input"))
      (node (ref "C17") (pin "1") (pinfunction "1_1") (pintype "input"))
      (node (ref "C18") (pin "1") (pinfunction "1_1") (pintype "input"))
      (node (ref "C19") (pin "2") (pinfunction "2_2") (pintype "input"))
      (node (ref "C2") (pin "1") (pinfunction "1_1") (pintype "input"))
      (node (ref "C20") (pin "1") (pinfunction "1_1") (pintype "input"))
      (node (ref "C21") (pin "1") (pinfunction "1_1") (pintype "input"))
      (node (ref "C22") (pin "1") (pinfunction "1_1") (pintype "input"))
      (node (ref "C23") (pin "1") (pinfunction "1_1") (pintype "input"))
      (node (ref "C25") (pin "1") (pinfunction "1_1") (pintype "input"))
      (node (ref "C34") (pin "1") (pinfunction "1_1") (pintype "input"))
      (node (ref "C35") (pin "2") (pinfunction "2_2") (pintype "input"))
      (node (ref "C37") (pin "2") (pinfunction "2_2") (pintype "input"))
      (node (ref "C38") (pin "1") (pinfunction "1_1") (pintype "input"))
      (node (ref "C39") (pin "1") (pinfunction "1_1") (pintype "input"))
      (node (ref "C4") (pin "1") (pinfunction "1_1") (pintype "input"))
      (node (ref "C40") (pin "1") (pinfunction "1_1") (pintype "input"))
      (node (ref "C41") (pin "1") (pinfunction "1_1") (pintype "input"))
      (node (ref "C42") (pin "2") (pinfunction "2_2") (pintype "input"))
      (node (ref "C43") (pin "1") (pinfunction "1_1") (pintype "input"))
      (node (ref "C46") (pin "2") (pinfunction "2_2") (pintype "input"))
      (node (ref "C48") (pin "1") (pinfunction "1_1") (pintype "input"))
      (node (ref "C5") (pin "1") (pinfunction "1_1") (pintype "input"))
      (node (ref "C50") (pin "1") (pinfunction "1_1") (pintype "input"))
      (node (ref "C6") (pin "1") (pinfunction "1_1") (pintype "input"))
      (node (ref "C7") (pin "1") (pinfunction "1_1") (pintype "input"))
      (node (ref "C8") (pin "1") (pinfunction "1_1") (pintype "input"))
      (node (ref "C9") (pin "2") (pinfunction "2_2") (pintype "input"))
      (node (ref "D12") (pin "1") (pinfunction "1_1") (pintype "input"))
      (node (ref "H5") (pin "3") (pinfunction "3_3") (pintype "input"))
      (node (ref "L3") (pin "1") (pinfunction "1_1") (pintype "input"))
      (node (ref "LC") (pin "1") (pinfunction "1_1") (pintype "unspecified"))
      (node (ref "LCD1") (pin "1") (pinfunction "VSS_1") (pintype "input"))
      (node (ref "LCD1") (pin "5") (pinfunction "RW_5") (pintype "input"))
      (node (ref "LDO1") (pin "1") (pinfunction "GND_1") (pintype "input"))
      (node (ref "R1") (pin "1") (pinfunction "1_1") (pintype "input"))
      (node (ref "R15") (pin "1") (pinfunction "1_1") (pintype "input"))
      (node (ref "R18") (pin "1") (pinfunction "1_1") (pintype "input"))
      (node (ref "R2") (pin "1") (pinfunction "1_1") (pintype "input"))
      (node (ref "R28") (pin "1") (pinfunction "1_1") (pintype "input"))
      (node (ref "R29") (pin "1") (pinfunction "1_1") (pintype "input"))
      (node (ref "R33") (pin "2") (pinfunction "2_2") (pintype "input"))
      (node (ref "R35") (pin "2") (pinfunction "2_2") (pintype "input"))
      (node (ref "R39") (pin "1") (pinfunction "1_1") (pintype "input"))
      (node (ref "R41") (pin "1") (pinfunction "1_1") (pintype "input"))
      (node (ref "R45") (pin "1") (pinfunction "1_1") (pintype "input"))
      (node (ref "R48") (pin "1") (pinfunction "1_1") (pintype "input"))
      (node (ref "R51") (pin "1") (pinfunction "1_1") (pintype "input"))
      (node (ref "R56") (pin "1") (pinfunction "1_1") (pintype "input"))
      (node (ref "R58") (pin "1") (pinfunction "1_1") (pintype "input"))
      (node (ref "R61") (pin "1") (pinfunction "1_1") (pintype "input"))
      (node (ref "R63") (pin "1") (pinfunction "1_1") (pintype "input"))
      (node (ref "R75") (pin "1") (pinfunction "1_1") (pintype "input"))
      (node (ref "R77") (pin "1") (pinfunction "1_1") (pintype "input"))
      (node (ref "R78") (pin "1") (pinfunction "1_1") (pintype "input"))
      (node (ref "R79") (pin "1") (pinfunction "1_1") (pintype "input"))
      (node (ref "R80") (pin "1") (pinfunction "1_1") (pintype "input"))
      (node (ref "R83") (pin "2") (pinfunction "2_2") (pintype "input"))
      (node (ref "SW1") (pin "3") (pinfunction "3_3") (pintype "input"))
      (node (ref "SW1") (pin "4") (pinfunction "4_4") (pintype "input"))
      (node (ref "SW2") (pin "3") (pinfunction "3_3") (pintype "input"))
      (node (ref "SW2") (pin "4") (pinfunction "4_4") (pintype "input"))
      (node (ref "U3") (pin "6") (pinfunction "E#_6") (pintype "input"))
      (node (ref "U3") (pin "8") (pinfunction "VSS_8") (pintype "input"))
      (node (ref "U32") (pin "13") (pinfunction "NC_13") (pintype "input"))
      (node (ref "U32") (pin "8") (pinfunction "GND_8") (pintype "input"))
      (node (ref "U33") (pin "2") (pinfunction "SE_2") (pintype "input"))
      (node (ref "U33") (pin "4") (pinfunction "GND_4") (pintype "input"))
      (node (ref "U35") (pin "1") (pinfunction "TEMP_1") (pintype "input"))
      (node (ref "U35") (pin "3") (pinfunction "GND_3") (pintype "input"))
      (node (ref "U37") (pin "2") (pinfunction "S_2") (pintype "input"))
      (node (ref "U6") (pin "15") (pinfunction "VSS_15") (pintype "input"))
      (node (ref "U8") (pin "6") (pinfunction "E#_6") (pintype "input"))
      (node (ref "U8") (pin "8") (pinfunction "VSS_8") (pintype "input"))
      (node (ref "USB1") (pin "1") (pinfunction "GND_1") (pintype "input"))
      (node (ref "USB1") (pin "12") (pinfunction "GND_12") (pintype "input"))
      (node (ref "USB1") (pin "13") (pinfunction "SHELL_13") (pintype "input"))
      (node (ref "USB1") (pin "14") (pinfunction "SHELL_14") (pintype "input"))
    )
    (net (code "16") (name "Net-(C3-Pad2)") (class "Default")
      (node (ref "C3") (pin "2") (pinfunction "2_2") (pintype "input"))
      (node (ref "C7") (pin "2") (pinfunction "2_2") (pintype "input"))
      (node (ref "R19") (pin "1") (pinfunction "1_1") (pintype "input"))
    )
    (net (code "17") (name "Net-(C4-Pad2)") (class "Default")
      (node (ref "C4") (pin "2") (pinfunction "2_2") (pintype "input"))
      (node (ref "R21") (pin "2") (pinfunction "2_2") (pintype "input"))
      (node (ref "R22") (pin "1") (pinfunction "1_1") (pintype "input"))
    )
    (net (code "18") (name "Net-(C5-Pad2)") (class "Default")
      (node (ref "C5") (pin "2") (pinfunction "2_2") (pintype "input"))
      (node (ref "R20") (pin "2") (pinfunction "2_2") (pintype "input"))
      (node (ref "R21") (pin "1") (pinfunction "1_1") (pintype "input"))
    )
    (net (code "19") (name "Net-(C6-Pad2)") (class "Default")
      (node (ref "C6") (pin "2") (pinfunction "2_2") (pintype "input"))
      (node (ref "R19") (pin "2") (pinfunction "2_2") (pintype "input"))
      (node (ref "R20") (pin "1") (pinfunction "1_1") (pintype "input"))
    )
    (net (code "20") (name "Net-(C24-Pad1)") (class "Default")
      (node (ref "C24") (pin "1") (pinfunction "1_1") (pintype "input"))
      (node (ref "C25") (pin "2") (pinfunction "2_2") (pintype "input"))
      (node (ref "R54") (pin "2") (pinfunction "2_2") (pintype "input"))
      (node (ref "R55") (pin "1") (pinfunction "1_1") (pintype "input"))
      (node (ref "R56") (pin "2") (pinfunction "2_2") (pintype "input"))
      (node (ref "R57") (pin "2") (pinfunction "2_2") (pintype "input"))
    )
    (net (code "21") (name "Net-(C44-Pad1)") (class "Default")
      (node (ref "C44") (pin "1") (pinfunction "1_1") (pintype "input"))
      (node (ref "R28") (pin "2") (pinfunction "2_2") (pintype "input"))
      (node (ref "R31") (pin "1") (pinfunction "1_1") (pintype "input"))
    )
    (net (code "22") (name "Net-(C44-Pad2)") (class "Default")
      (node (ref "C44") (pin "2") (pinfunction "2_2") (pintype "input"))
      (node (ref "LP") (pin "1") (pinfunction "1_1") (pintype "unspecified"))
    )
    (net (code "23") (name "Net-(C45-Pad1)") (class "Default")
      (node (ref "C45") (pin "1") (pinfunction "1_1") (pintype "input"))
      (node (ref "R29") (pin "2") (pinfunction "2_2") (pintype "input"))
      (node (ref "R30") (pin "1") (pinfunction "1_1") (pintype "input"))
    )
    (net (code "24") (name "Net-(C45-Pad2)") (class "Default")
      (node (ref "C45") (pin "2") (pinfunction "2_2") (pintype "input"))
      (node (ref "HP") (pin "1") (pinfunction "1_1") (pintype "unspecified"))
    )
    (net (code "25") (name "Net-(D1-A)") (class "Default")
      (node (ref "D1") (pin "2") (pinfunction "A_2") (pintype "input"))
      (node (ref "L3") (pin "2") (pinfunction "2_2") (pintype "input"))
      (node (ref "U34") (pin "2") (pinfunction "SE_2") (pintype "input"))
    )
    (net (code "26") (name "Net-(D2-A)") (class "Default")
      (node (ref "D2") (pin "1") (pinfunction "A_1") (pintype "input"))
      (node (ref "Q4") (pin "1") (pinfunction "B_1") (pintype "input"))
      (node (ref "Q5") (pin "1") (pinfunction "B_1") (pintype "input"))
      (node (ref "R11") (pin "1") (pinfunction "1_1") (pintype "input"))
    )
    (net (code "27") (name "Net-(D2-C)") (class "Default")
      (node (ref "D2") (pin "2") (pinfunction "C_2") (pintype "input"))
      (node (ref "D3") (pin "1") (pinfunction "A_1") (pintype "input"))
      (node (ref "U1") (pin "7") (pinfunction "OUT2_7") (pintype "input"))
    )
    (net (code "28") (name "Net-(D3-C)") (class "Default")
      (node (ref "D3") (pin "2") (pinfunction "C_2") (pintype "input"))
      (node (ref "Q2") (pin "1") (pinfunction "B_1") (pintype "input"))
      (node (ref "Q3") (pin "1") (pinfunction "B_1") (pintype "input"))
      (node (ref "R12") (pin "2") (pinfunction "2_2") (pintype "input"))
    )
    (net (code "29") (name "Net-(D4-A)") (class "Default")
      (node (ref "C10") (pin "2") (pinfunction "2_2") (pintype "input"))
      (node (ref "C11") (pin "2") (pinfunction "2_2") (pintype "input"))
      (node (ref "D4") (pin "2") (pinfunction "A_2") (pintype "input"))
      (node (ref "D5") (pin "2") (pinfunction "A_2") (pintype "input"))
    )
    (net (code "30") (name "Net-(D4-K)") (class "Default")
      (node (ref "C10") (pin "1") (pinfunction "1_1") (pintype "input"))
      (node (ref "D12") (pin "2") (pinfunction "2_2") (pintype "input"))
      (node (ref "D4") (pin "1") (pinfunction "K_1") (pintype "input"))
      (node (ref "Q7") (pin "2") (pinfunction "S_2") (pintype "input"))
      (node (ref "R6") (pin "1") (pinfunction "1_1") (pintype "input"))
      (node (ref "R71") (pin "1") (pinfunction "1_1") (pintype "input"))
    )
    (net (code "31") (name "Net-(D5-K)") (class "Default")
      (node (ref "C11") (pin "1") (pinfunction "1_1") (pintype "input"))
      (node (ref "D5") (pin "1") (pinfunction "K_1") (pintype "input"))
      (node (ref "HC") (pin "1") (pinfunction "1_1") (pintype "unspecified"))
    )
    (net (code "32") (name "Net-(D6-C)") (class "Default")
      (node (ref "D6") (pin "2") (pinfunction "C_2") (pintype "input"))
      (node (ref "D7") (pin "1") (pinfunction "A_1") (pintype "input"))
      (node (ref "R30") (pin "2") (pinfunction "2_2") (pintype "input"))
      (node (ref "U2") (pin "3") (pinfunction "POS1_3") (pintype "input"))
    )
    (net (code "33") (name "Net-(D8-C)") (class "Default")
      (node (ref "D8") (pin "2") (pinfunction "C_2") (pintype "input"))
      (node (ref "D9") (pin "1") (pinfunction "A_1") (pintype "input"))
      (node (ref "R31") (pin "2") (pinfunction "2_2") (pintype "input"))
      (node (ref "U2") (pin "12") (pinfunction "POS4_12") (pintype "input"))
    )
    (net (code "34") (name "Net-(D13-A)") (class "Default")
      (node (ref "D13") (pin "2") (pinfunction "A_2") (pintype "input"))
      (node (ref "L2") (pin "2") (pinfunction "2_2") (pintype "input"))
      (node (ref "U33") (pin "1") (pinfunction "SC_1") (pintype "input"))
    )
    (net (code "35") (name "Net-(LCD1-DB4)") (class "Default")
      (node (ref "LCD1") (pin "11") (pinfunction "DB4_11") (pintype "input"))
      (node (ref "U32") (pin "2") (pinfunction "Q2_2") (pintype "input"))
    )
    (net (code "36") (name "Net-(LCD1-DB5)") (class "Default")
      (node (ref "LCD1") (pin "12") (pinfunction "DB5_12") (pintype "input"))
      (node (ref "U32") (pin "3") (pinfunction "Q3_3") (pintype "input"))
    )
    (net (code "37") (name "Net-(LCD1-DB6)") (class "Default")
      (node (ref "LCD1") (pin "13") (pinfunction "DB6_13") (pintype "input"))
      (node (ref "U32") (pin "4") (pinfunction "Q4_4") (pintype "input"))
    )
    (net (code "38") (name "Net-(LCD1-DB7)") (class "Default")
      (node (ref "LCD1") (pin "14") (pinfunction "DB7_14") (pintype "input"))
      (node (ref "U32") (pin "5") (pinfunction "Q5_5") (pintype "input"))
    )
    (net (code "39") (name "Net-(LCD1-E)") (class "Default")
      (node (ref "LCD1") (pin "6") (pinfunction "E_6") (pintype "input"))
      (node (ref "U32") (pin "1") (pinfunction "Q1_1") (pintype "input"))
    )
    (net (code "40") (name "Net-(LCD1-K)") (class "Default")
      (node (ref "LCD1") (pin "16") (pinfunction "K_16") (pintype "input"))
      (node (ref "R33") (pin "1") (pinfunction "1_1") (pintype "input"))
    )
    (net (code "41") (name "Net-(LCD1-RS)") (class "Default")
      (node (ref "LCD1") (pin "4") (pinfunction "RS_4") (pintype "input"))
      (node (ref "U32") (pin "15") (pinfunction "Q0_15") (pintype "input"))
    )
    (net (code "42") (name "Net-(LCD1-V0)") (class "Default")
      (node (ref "LCD1") (pin "3") (pinfunction "V0_3") (pintype "input"))
      (node (ref "R34") (pin "2") (pinfunction "2_2") (pintype "input"))
    )
    (net (code "43") (name "Net-(LDO1-VDD)") (class "Default")
      (node (ref "C12") (pin "1") (pinfunction "1_1") (pintype "input"))
      (node (ref "C48") (pin "2") (pinfunction "2_2") (pintype "input"))
      (node (ref "LDO1") (pin "3") (pinfunction "VDD_3") (pintype "input"))
      (node (ref "R26") (pin "2") (pinfunction "2_2") (pintype "input"))
      (node (ref "R72") (pin "2") (pinfunction "2_2") (pintype "input"))
      (node (ref "SW3") (pin "2") (pinfunction "2_2") (pintype "input"))
      (node (ref "SW3") (pin "3") (pinfunction "3_3") (pintype "input"))
      (node (ref "U33") (pin "6") (pinfunction "VCC_6") (pintype "input"))
      (node (ref "U34") (pin "6") (pinfunction "VCC_6") (pintype "input"))
    )
    (net (code "44") (name "Net-(LED1-A)") (class "Default")
      (node (ref "LED1") (pin "2") (pinfunction "A_2") (pintype "input"))
      (node (ref "R81") (pin "2") (pinfunction "2_2") (pintype "input"))
    )
    (net (code "45") (name "Net-(LED1-C)") (class "Default")
      (node (ref "C50") (pin "2") (pinfunction "2_2") (pintype "input"))
      (node (ref "LED1") (pin "1") (pinfunction "C_1") (pintype "input"))
      (node (ref "LED2") (pin "1") (pinfunction "C_1") (pintype "input"))
      (node (ref "U35") (pin "4") (pinfunction "Vcc_4") (pintype "input"))
      (node (ref "U35") (pin "8") (pinfunction "CE_8") (pintype "input"))
      (node (ref "USB1") (pin "11") (pinfunction "VBUS_11") (pintype "input"))
      (node (ref "USB1") (pin "2") (pinfunction "VBUS_2") (pintype "input"))
    )
    (net (code "46") (name "Net-(LED2-A)") (class "Default")
      (node (ref "LED2") (pin "2") (pinfunction "A_2") (pintype "input"))
      (node (ref "R82") (pin "2") (pinfunction "2_2") (pintype "input"))
    )
    (net (code "47") (name "Net-(Q2-E)") (class "Default")
      (node (ref "Q2") (pin "2") (pinfunction "E_2") (pintype "input"))
      (node (ref "R9") (pin "1") (pinfunction "1_1") (pintype "input"))
    )
    (net (code "48") (name "Net-(Q3-E)") (class "Default")
      (node (ref "Q3") (pin "2") (pinfunction "E_2") (pintype "input"))
      (node (ref "R8") (pin "1") (pinfunction "1_1") (pintype "input"))
    )
    (net (code "49") (name "Net-(Q4-E)") (class "Default")
      (node (ref "Q4") (pin "2") (pinfunction "E_2") (pintype "input"))
      (node (ref "R10") (pin "2") (pinfunction "2_2") (pintype "input"))
    )
    (net (code "50") (name "Net-(Q5-E)") (class "Default")
      (node (ref "Q5") (pin "2") (pinfunction "E_2") (pintype "input"))
      (node (ref "R7") (pin "2") (pinfunction "2_2") (pintype "input"))
    )
    (net (code "51") (name "Net-(Q6-D)") (class "Default")
      (node (ref "Q6") (pin "3") (pinfunction "D_3") (pintype "input"))
      (node (ref "Q7") (pin "3") (pinfunction "D_3") (pintype "input"))
    )
    (net (code "52") (name "Net-(Q6-G)") (class "Default")
      (node (ref "Q6") (pin "1") (pinfunction "G_1") (pintype "input"))
      (node (ref "Q7") (pin "1") (pinfunction "G_1") (pintype "input"))
      (node (ref "U8") (pin "14") (pinfunction "ZA_14") (pintype "input"))
    )
    (net (code "53") (name "Net-(Q6-S)") (class "Default")
      (node (ref "Q6") (pin "2") (pinfunction "S_2") (pintype "input"))
      (node (ref "R5") (pin "1") (pinfunction "1_1") (pintype "input"))
      (node (ref "R69") (pin "1") (pinfunction "1_1") (pintype "input"))
      (node (ref "R71") (pin "2") (pinfunction "2_2") (pintype "input"))
    )
    (net (code "54") (name "Net-(R1-Pad2)") (class "Default")
      (node (ref "R1") (pin "2") (pinfunction "2_2") (pintype "input"))
      (node (ref "R2") (pin "2") (pinfunction "2_2") (pintype "input"))
      (node (ref "R34") (pin "1") (pinfunction "1_1") (pintype "input"))
    )
    (net (code "55") (name "Net-(R10-Pad1)") (class "Default")
      (node (ref "R10") (pin "1") (pinfunction "1_1") (pintype "input"))
      (node (ref "R3") (pin "1") (pinfunction "1_1") (pintype "input"))
      (node (ref "R69") (pin "2") (pinfunction "2_2") (pintype "input"))
      (node (ref "R7") (pin "1") (pinfunction "1_1") (pintype "input"))
      (node (ref "R8") (pin "2") (pinfunction "2_2") (pintype "input"))
      (node (ref "R9") (pin "2") (pinfunction "2_2") (pintype "input"))
    )
    (net (code "56") (name "Net-(U1-NEG1)") (class "Default")
      (node (ref "R13") (pin "2") (pinfunction "2_2") (pintype "input"))
      (node (ref "U1") (pin "1") (pinfunction "OUT1_1") (pintype "input"))
      (node (ref "U1") (pin "2") (pinfunction "NEG1_2") (pintype "input"))
    )
    (net (code "57") (name "Net-(U1-NEG2)") (class "Default")
      (node (ref "R13") (pin "1") (pinfunction "1_1") (pintype "input"))
      (node (ref "R17") (pin "2") (pinfunction "2_2") (pintype "input"))
      (node (ref "U1") (pin "6") (pinfunction "NEG2_6") (pintype "input"))
    )
    (net (code "58") (name "Net-(U1-NEG3)") (class "Default")
      (node (ref "R17") (pin "1") (pinfunction "1_1") (pintype "input"))
      (node (ref "U1") (pin "8") (pinfunction "OUT3_8") (pintype "input"))
      (node (ref "U1") (pin "9") (pinfunction "NEG3_9") (pintype "input"))
    )
    (net (code "59") (name "Net-(U1-NEG4)") (class "Default")
      (node (ref "R16") (pin "2") (pinfunction "2_2") (pintype "input"))
      (node (ref "U1") (pin "13") (pinfunction "NEG4_13") (pintype "input"))
      (node (ref "U1") (pin "14") (pinfunction "OUT4_14") (pintype "input"))
    )
    (net (code "60") (name "Net-(U1-POS1)") (class "Default")
      (node (ref "U1") (pin "3") (pinfunction "POS1_3") (pintype "input"))
      (node (ref "U8") (pin "4") (pinfunction "ZC_4") (pintype "input"))
    )
    (net (code "61") (name "Net-(U1-POS2)") (class "Default")
      (node (ref "R15") (pin "2") (pinfunction "2_2") (pintype "input"))
      (node (ref "R16") (pin "1") (pinfunction "1_1") (pintype "input"))
      (node (ref "U1") (pin "5") (pinfunction "POS2_5") (pintype "input"))
    )
    (net (code "62") (name "Net-(U1-POS3)") (class "Default")
      (node (ref "C3") (pin "1") (pinfunction "1_1") (pintype "input"))
      (node (ref "R18") (pin "2") (pinfunction "2_2") (pintype "input"))
      (node (ref "U1") (pin "10") (pinfunction "POS3_10") (pintype "input"))
    )
    (net (code "63") (name "Net-(U1-POS4)") (class "Default")
      (node (ref "U1") (pin "12") (pinfunction "POS4_12") (pintype "input"))
      (node (ref "U8") (pin "15") (pinfunction "ZB_15") (pintype "input"))
    )
    (net (code "64") (name "Net-(U2-NEG1)") (class "Default")
      (node (ref "R42") (pin "1") (pinfunction "1_1") (pintype "input"))
      (node (ref "U2") (pin "1") (pinfunction "OUT1_1") (pintype "input"))
      (node (ref "U2") (pin "2") (pinfunction "NEG1_2") (pintype "input"))
    )
    (net (code "65") (name "Net-(U2-NEG2)") (class "Default")
      (node (ref "C30") (pin "1") (pinfunction "1_1") (pintype "input"))
      (node (ref "R36") (pin "2") (pinfunction "2_2") (pintype "input"))
      (node (ref "R38") (pin "1") (pinfunction "1_1") (pintype "input"))
      (node (ref "R39") (pin "2") (pinfunction "2_2") (pintype "input"))
      (node (ref "U2") (pin "6") (pinfunction "NEG2_6") (pintype "input"))
    )
    (net (code "66") (name "Net-(U2-NEG3)") (class "Default")
      (node (ref "R37") (pin "1") (pinfunction "1_1") (pintype "input"))
      (node (ref "R42") (pin "2") (pinfunction "2_2") (pintype "input"))
      (node (ref "U2") (pin "9") (pinfunction "NEG3_9") (pintype "input"))
    )
    (net (code "67") (name "Net-(U2-NEG4)") (class "Default")
      (node (ref "R40") (pin "2") (pinfunction "2_2") (pintype "input"))
      (node (ref "U2") (pin "13") (pinfunction "NEG4_13") (pintype "input"))
      (node (ref "U2") (pin "14") (pinfunction "OUT4_14") (pintype "input"))
    )
    (net (code "68") (name "Net-(U2-OUT2)") (class "Default")
      (node (ref "C30") (pin "2") (pinfunction "2_2") (pintype "input"))
      (node (ref "R36") (pin "1") (pinfunction "1_1") (pintype "input"))
      (node (ref "R38") (pin "2") (pinfunction "2_2") (pintype "input"))
      (node (ref "R43") (pin "2") (pinfunction "2_2") (pintype "input"))
      (node (ref "R44") (pin "2") (pinfunction "2_2") (pintype "input"))
      (node (ref "U2") (pin "7") (pinfunction "OUT2_7") (pintype "input"))
      (node (ref "U3") (pin "1") (pinfunction "Y1B_1") (pintype "input"))
    )
    (net (code "69") (name "Net-(U2-OUT3)") (class "Default")
      (node (ref "R37") (pin "2") (pinfunction "2_2") (pintype "input"))
      (node (ref "R46") (pin "2") (pinfunction "2_2") (pintype "input"))
      (node (ref "R47") (pin "2") (pinfunction "2_2") (pintype "input"))
      (node (ref "U2") (pin "8") (pinfunction "OUT3_8") (pintype "input"))
      (node (ref "U3") (pin "3") (pinfunction "Y1C_3") (pintype "input"))
    )
    (net (code "70") (name "Net-(U2-POS2)") (class "Default")
      (node (ref "C31") (pin "2") (pinfunction "2_2") (pintype "input"))
      (node (ref "R63") (pin "2") (pinfunction "2_2") (pintype "input"))
      (node (ref "U2") (pin "5") (pinfunction "POS2_5") (pintype "input"))
    )
    (net (code "71") (name "Net-(U2-POS3)") (class "Default")
      (node (ref "R40") (pin "1") (pinfunction "1_1") (pintype "input"))
      (node (ref "R41") (pin "2") (pinfunction "2_2") (pintype "input"))
      (node (ref "U2") (pin "10") (pinfunction "POS3_10") (pintype "input"))
    )
    (net (code "72") (name "Net-(U3-Y0A)") (class "Default")
      (node (ref "R49") (pin "1") (pinfunction "1_1") (pintype "input"))
      (node (ref "R50") (pin "1") (pinfunction "1_1") (pintype "input"))
      (node (ref "R51") (pin "2") (pinfunction "2_2") (pintype "input"))
      (node (ref "U3") (pin "12") (pinfunction "Y0A_12") (pintype "input"))
    )
    (net (code "73") (name "Net-(U3-Y0B)") (class "Default")
      (node (ref "R43") (pin "1") (pinfunction "1_1") (pintype "input"))
      (node (ref "R44") (pin "1") (pinfunction "1_1") (pintype "input"))
      (node (ref "R45") (pin "2") (pinfunction "2_2") (pintype "input"))
      (node (ref "U3") (pin "2") (pinfunction "Y0B_2") (pintype "input"))
    )
    (net (code "74") (name "Net-(U3-Y0C)") (class "Default")
      (node (ref "R46") (pin "1") (pinfunction "1_1") (pintype "input"))
      (node (ref "R47") (pin "1") (pinfunction "1_1") (pintype "input"))
      (node (ref "R48") (pin "2") (pinfunction "2_2") (pintype "input"))
      (node (ref "U3") (pin "5") (pinfunction "Y0C_5") (pintype "input"))
    )
    (net (code "75") (name "Net-(U3-ZA)") (class "Default")
      (node (ref "C26") (pin "1") (pinfunction "1_1") (pintype "input"))
      (node (ref "U3") (pin "14") (pinfunction "ZA_14") (pintype "input"))
    )
    (net (code "76") (name "Net-(U3-ZB)") (class "Default")
      (node (ref "C27") (pin "1") (pinfunction "1_1") (pintype "input"))
      (node (ref "U3") (pin "15") (pinfunction "ZB_15") (pintype "input"))
    )
    (net (code "77") (name "Net-(U3-ZC)") (class "Default")
      (node (ref "C31") (pin "1") (pinfunction "1_1") (pintype "input"))
      (node (ref "U3") (pin "4") (pinfunction "ZC_4") (pintype "input"))
    )
    (net (code "78") (name "Net-(U6-BOOT0)") (class "Default")
      (node (ref "R35") (pin "1") (pinfunction "1_1") (pintype "input"))
      (node (ref "U6") (pin "1") (pinfunction "BOOT0_1") (pintype "input"))
    )
    (net (code "79") (name "Net-(U6-NRST)") (class "Default")
      (node (ref "C14") (pin "1") (pinfunction "1_1") (pintype "input"))
      (node (ref "U6") (pin "4") (pinfunction "NRST_4") (pintype "bidirectional"))
    )
    (net (code "80") (name "Net-(U6-PA6)") (class "Default")
      (node (ref "SW1") (pin "1") (pinfunction "1_1") (pintype "input"))
      (node (ref "SW1") (pin "2") (pinfunction "2_2") (pintype "input"))
      (node (ref "U6") (pin "12") (pinfunction "PA6_12") (pintype "bidirectional"))
    )
    (net (code "81") (name "Net-(U6-PA9)") (class "Default")
      (node (ref "SW2") (pin "1") (pinfunction "1_1") (pintype "input"))
      (node (ref "SW2") (pin "2") (pinfunction "2_2") (pintype "input"))
      (node (ref "U6") (pin "17") (pinfunction "PA9_17") (pintype "bidirectional"))
    )
    (net (code "82") (name "Net-(U6-PA13(SWDIO))") (class "Default")
      (node (ref "H5") (pin "2") (pinfunction "2_2") (pintype "input"))
      (node (ref "U6") (pin "19") (pinfunction "PA13(SWDIO)_19") (pintype "bidirectional"))
    )
    (net (code "83") (name "Net-(U6-PA14(SWCLK))") (class "Default")
      (node (ref "H5") (pin "1") (pinfunction "1_1") (pintype "input"))
      (node (ref "U6") (pin "20") (pinfunction "PA14(SWCLK)_20") (pintype "bidirectional"))
    )
    (net (code "84") (name "Net-(U6-PF0-OSC_IN(PF0))") (class "Default")
      (node (ref "C15") (pin "1") (pinfunction "1_1") (pintype "input"))
      (node (ref "U6") (pin "2") (pinfunction "PF0-OSC_IN(PF0)_2") (pintype "bidirectional"))
      (node (ref "X1") (pin "1") (pinfunction "OSC1_1") (pintype "input"))
    )
    (net (code "85") (name "Net-(U6-PF1-OSC_OUT(PF1))") (class "Default")
      (node (ref "C16") (pin "1") (pinfunction "1_1") (pintype "input"))
      (node (ref "U6") (pin "3") (pinfunction "PF1-OSC_OUT(PF1)_3") (pintype "bidirectional"))
      (node (ref "X1") (pin "2") (pinfunction "OSC2_2") (pintype "input"))
    )
    (net (code "86") (name "Net-(U6-VDDA)") (class "Default")
      (node (ref "C17") (pin "2") (pinfunction "2_2") (pintype "input"))
      (node (ref "L1") (pin "1") (pinfunction "1_1") (pintype "input"))
      (node (ref "U6") (pin "5") (pinfunction "VDDA_5") (pintype "input"))
    )
    (net (code "87") (name "Net-(U8-Y0A)") (class "Default")
      (node (ref "R23") (pin "2") (pinfunction "2_2") (pintype "input"))
      (node (ref "U8") (pin "12") (pinfunction "Y0A_12") (pintype "input"))
    )
    (net (code "88") (name "Net-(U8-Y0B)") (class "Default")
      (node (ref "R5") (pin "2") (pinfunction "2_2") (pintype "input"))
      (node (ref "U8") (pin "2") (pinfunction "Y0B_2") (pintype "input"))
      (node (ref "U8") (pin "3") (pinfunction "Y1C_3") (pintype "input"))
    )
    (net (code "89") (name "Net-(U8-Y0C)") (class "Default")
      (node (ref "R3") (pin "2") (pinfunction "2_2") (pintype "input"))
      (node (ref "U8") (pin "5") (pinfunction "Y0C_5") (pintype "input"))
    )
    (net (code "90") (name "Net-(U8-Y1A)") (class "Default")
      (node (ref "R24") (pin "2") (pinfunction "2_2") (pintype "input"))
      (node (ref "U8") (pin "13") (pinfunction "Y1A_13") (pintype "input"))
    )
    (net (code "91") (name "Net-(U8-Y1B)") (class "Default")
      (node (ref "R6") (pin "2") (pinfunction "2_2") (pintype "input"))
      (node (ref "U8") (pin "1") (pinfunction "Y1B_1") (pintype "input"))
    )
    (net (code "92") (name "Net-(U11A-IN1+)") (class "Default")
      (node (ref "C26") (pin "2") (pinfunction "2_2") (pintype "input"))
      (node (ref "R57") (pin "1") (pinfunction "1_1") (pintype "input"))
      (node (ref "U11") (pin "3") (pinfunction "IN1+_3") (pintype "input"))
    )
    (net (code "93") (name "Net-(U11A-IN1-)") (class "Default")
      (node (ref "C28") (pin "1") (pinfunction "1_1") (pintype "input"))
      (node (ref "R52") (pin "1") (pinfunction "1_1") (pintype "input"))
      (node (ref "R53") (pin "2") (pinfunction "2_2") (pintype "input"))
      (node (ref "R54") (pin "1") (pinfunction "1_1") (pintype "input"))
      (node (ref "U11") (pin "2") (pinfunction "IN1-_2") (pintype "input"))
    )
    (net (code "94") (name "Net-(U11A-OUT1)") (class "Default")
      (node (ref "C28") (pin "2") (pinfunction "2_2") (pintype "input"))
      (node (ref "R52") (pin "2") (pinfunction "2_2") (pintype "input"))
      (node (ref "R53") (pin "1") (pinfunction "1_1") (pintype "input"))
      (node (ref "R62") (pin "1") (pinfunction "1_1") (pintype "input"))
      (node (ref "U11") (pin "1") (pinfunction "OUT1_1") (pintype "output"))
    )
    (net (code "95") (name "Net-(U11B-IN2+)") (class "Default")
      (node (ref "C27") (pin "2") (pinfunction "2_2") (pintype "input"))
      (node (ref "R58") (pin "2") (pinfunction "2_2") (pintype "input"))
      (node (ref "U11") (pin "5") (pinfunction "IN2+_5") (pintype "input"))
    )
    (net (code "96") (name "Net-(U11B-IN2-)") (class "Default")
      (node (ref "C29") (pin "1") (pinfunction "1_1") (pintype "input"))
      (node (ref "R59") (pin "1") (pinfunction "1_1") (pintype "input"))
      (node (ref "R60") (pin "2") (pinfunction "2_2") (pintype "input"))
      (node (ref "R61") (pin "2") (pinfunction "2_2") (pintype "input"))
      (node (ref "U11") (pin "6") (pinfunction "IN2-_6") (pintype "input"))
    )
    (net (code "97") (name "Net-(U11B-OUT2)") (class "Default")
      (node (ref "C29") (pin "2") (pinfunction "2_2") (pintype "input"))
      (node (ref "R49") (pin "2") (pinfunction "2_2") (pintype "input"))
      (node (ref "R50") (pin "2") (pinfunction "2_2") (pintype "input"))
      (node (ref "R59") (pin "2") (pinfunction "2_2") (pintype "input"))
      (node (ref "R60") (pin "1") (pinfunction "1_1") (pintype "input"))
      (node (ref "U11") (pin "7") (pinfunction "OUT2_7") (pintype "output"))
      (node (ref "U3") (pin "13") (pinfunction "Y1A_13") (pintype "input"))
    )
    (net (code "98") (name "Net-(U33-CT)") (class "Default")
      (node (ref "C46") (pin "1") (pinfunction "1_1") (pintype "input"))
      (node (ref "U33") (pin "3") (pinfunction "CT_3") (pintype "input"))
    )
    (net (code "99") (name "Net-(U33-DC)") (class "Default")
      (node (ref "R73") (pin "1") (pinfunction "1_1") (pintype "input"))
      (node (ref "U33") (pin "8") (pinfunction "DC_8") (pintype "input"))
    )
    (net (code "100") (name "Net-(U33-FB)") (class "Default")
      (node (ref "R74") (pin "1") (pinfunction "1_1") (pintype "input"))
      (node (ref "R75") (pin "2") (pinfunction "2_2") (pintype "input"))
      (node (ref "U33") (pin "5") (pinfunction "FB_5") (pintype "input"))
    )
    (net (code "101") (name "Net-(U33-IPK)") (class "Default")
      (node (ref "L2") (pin "1") (pinfunction "1_1") (pintype "input"))
      (node (ref "R72") (pin "1") (pinfunction "1_1") (pintype "input"))
      (node (ref "R73") (pin "2") (pinfunction "2_2") (pintype "input"))
      (node (ref "U33") (pin "7") (pinfunction "IPK_7") (pintype "input"))
    )
    (net (code "102") (name "Net-(U34-CT)") (class "Default")
      (node (ref "C47") (pin "2") (pinfunction "2_2") (pintype "input"))
      (node (ref "U34") (pin "3") (pinfunction "CT_3") (pintype "input"))
    )
    (net (code "103") (name "Net-(U34-DC)") (class "Default")
      (node (ref "R26") (pin "1") (pinfunction "1_1") (pintype "input"))
      (node (ref "U34") (pin "1") (pinfunction "SC_1") (pintype "input"))
      (node (ref "U34") (pin "7") (pinfunction "IPK_7") (pintype "input"))
      (node (ref "U34") (pin "8") (pinfunction "DC_8") (pintype "input"))
    )
    (net (code "104") (name "Net-(U34-FB)") (class "Default")
      (node (ref "R76") (pin "1") (pinfunction "1_1") (pintype "input"))
      (node (ref "R77") (pin "2") (pinfunction "2_2") (pintype "input"))
      (node (ref "U34") (pin "5") (pinfunction "FB_5") (pintype "input"))
    )
    (net (code "105") (name "Net-(U35-BAT)") (class "Default")
      (node (ref "C13") (pin "2") (pinfunction "2_2") (pintype "input"))
      (node (ref "H6") (pin "1") (pinfunction "1_1") (pintype "unspecified"))
      (node (ref "R84") (pin "1") (pinfunction "1_1") (pintype "input"))
      (node (ref "SW3") (pin "1") (pinfunction "1_1") (pintype "input"))
      (node (ref "U35") (pin "5") (pinfunction "BAT_5") (pintype "input"))
    )
    (net (code "106") (name "Net-(U35-CHRG#)") (class "Default")
      (node (ref "R81") (pin "1") (pinfunction "1_1") (pintype "input"))
      (node (ref "U35") (pin "7") (pinfunction "CHRG#_7") (pintype "input"))
    )
    (net (code "107") (name "Net-(U35-PROG)") (class "Default")
      (node (ref "R80") (pin "2") (pinfunction "2_2") (pintype "input"))
      (node (ref "U35") (pin "2") (pinfunction "PROG_2") (pintype "input"))
    )
    (net (code "108") (name "Net-(U35-STDBY#)") (class "Default")
      (node (ref "R82") (pin "1") (pinfunction "1_1") (pintype "input"))
      (node (ref "U35") (pin "6") (pinfunction "STDBY#_6") (pintype "input"))
    )
    (net (code "109") (name "Net-(U36-CS)") (class "Default")
      (node (ref "R83") (pin "1") (pinfunction "1_1") (pintype "input"))
      (node (ref "U36") (pin "2") (pinfunction "CS_2") (pintype "input"))
    )
    (net (code "110") (name "Net-(U36-GND)") (class "Default")
      (node (ref "C49") (pin "1") (pinfunction "1_1") (pintype "input"))
      (node (ref "H7") (pin "1") (pinfunction "1_1") (pintype "unspecified"))
      (node (ref "U36") (pin "6") (pinfunction "GND_6") (pintype "input"))
      (node (ref "U38") (pin "2") (pinfunction "S_2") (pintype "input"))
    )
    (net (code "111") (name "Net-(U36-OC)") (class "Default")
      (node (ref "U36") (pin "3") (pinfunction "OC_3") (pintype "input"))
      (node (ref "U37") (pin "1") (pinfunction "G_1") (pintype "input"))
    )
    (net (code "112") (name "Net-(U36-OD)") (class "Default")
      (node (ref "U36") (pin "1") (pinfunction "OD_1") (pintype "input"))
      (node (ref "U38") (pin "1") (pinfunction "G_1") (pintype "input"))
    )
    (net (code "113") (name "Net-(U36-VCC)") (class "Default")
      (node (ref "C49") (pin "2") (pinfunction "2_2") (pintype "input"))
      (node (ref "R84") (pin "2") (pinfunction "2_2") (pintype "input"))
      (node (ref "U36") (pin "5") (pinfunction "VCC_5") (pintype "input"))
    )
    (net (code "114") (name "Net-(U37-D)") (class "Default")
      (node (ref "U37") (pin "3") (pinfunction "D_3") (pintype "input"))
      (node (ref "U38") (pin "3") (pinfunction "D_3") (pintype "input"))
    )
    (net (code "115") (name "Net-(USB1-CC1)") (class "Default")
      (node (ref "R78") (pin "2") (pinfunction "2_2") (pintype "input"))
      (node (ref "USB1") (pin "4") (pinfunction "CC1_4") (pintype "input"))
    )
    (net (code "116") (name "Net-(USB1-CC2)") (class "Default")
      (node (ref "R79") (pin "2") (pinfunction "2_2") (pintype "input"))
      (node (ref "USB1") (pin "10") (pinfunction "CC2_10") (pintype "input"))
    )
    (net (code "117") (name "unconnected-(LCD1-DB0-Pad7)") (class "Default")
      (node (ref "LCD1") (pin "7") (pinfunction "DB0_7") (pintype "input+no_connect"))
    )
    (net (code "118") (name "unconnected-(LCD1-DB1-Pad8)") (class "Default")
      (node (ref "LCD1") (pin "8") (pinfunction "DB1_8") (pintype "input+no_connect"))
    )
    (net (code "119") (name "unconnected-(LCD1-DB2-Pad9)") (class "Default")
      (node (ref "LCD1") (pin "9") (pinfunction "DB2_9") (pintype "input+no_connect"))
    )
    (net (code "120") (name "unconnected-(LCD1-DB3-Pad10)") (class "Default")
      (node (ref "LCD1") (pin "10") (pinfunction "DB3_10") (pintype "input+no_connect"))
    )
    (net (code "121") (name "unconnected-(U32-Q6-Pad6)") (class "Default")
      (node (ref "U32") (pin "6") (pinfunction "Q6_6") (pintype "input"))
    )
    (net (code "122") (name "unconnected-(U32-Q7&apos;-Pad9)") (class "Default")
      (node (ref "U32") (pin "9") (pinfunction "Q7&apos;_9") (pintype "input"))
    )
    (net (code "123") (name "unconnected-(U32-Q7-Pad7)") (class "Default")
      (node (ref "U32") (pin "7") (pinfunction "Q7_7") (pintype "input"))
    )
    (net (code "124") (name "unconnected-(U36-TD-Pad4)") (class "Default")
      (node (ref "U36") (pin "4") (pinfunction "TD_4") (pintype "input+no_connect"))
    )
    (net (code "125") (name "unconnected-(USB1-DN1-Pad7)") (class "Default")
      (node (ref "USB1") (pin "7") (pinfunction "DN1_7") (pintype "input+no_connect"))
    )
    (net (code "126") (name "unconnected-(USB1-DN2-Pad5)") (class "Default")
      (node (ref "USB1") (pin "5") (pinfunction "DN2_5") (pintype "input+no_connect"))
    )
    (net (code "127") (name "unconnected-(USB1-DP1-Pad6)") (class "Default")
      (node (ref "USB1") (pin "6") (pinfunction "DP1_6") (pintype "input+no_connect"))
    )
    (net (code "128") (name "unconnected-(USB1-DP2-Pad8)") (class "Default")
      (node (ref "USB1") (pin "8") (pinfunction "DP2_8") (pintype "input+no_connect"))
    )
    (net (code "129") (name "unconnected-(USB1-SBU1-Pad9)") (class "Default")
      (node (ref "USB1") (pin "9") (pinfunction "SBU1_9") (pintype "input+no_connect"))
    )
    (net (code "130") (name "unconnected-(USB1-SBU2-Pad3)") (class "Default")
      (node (ref "USB1") (pin "3") (pinfunction "SBU2_3") (pintype "input+no_connect"))
    )
  )
)
